# Esquematico.net
KiCad netlist of a schematic drawn in EasyEDA
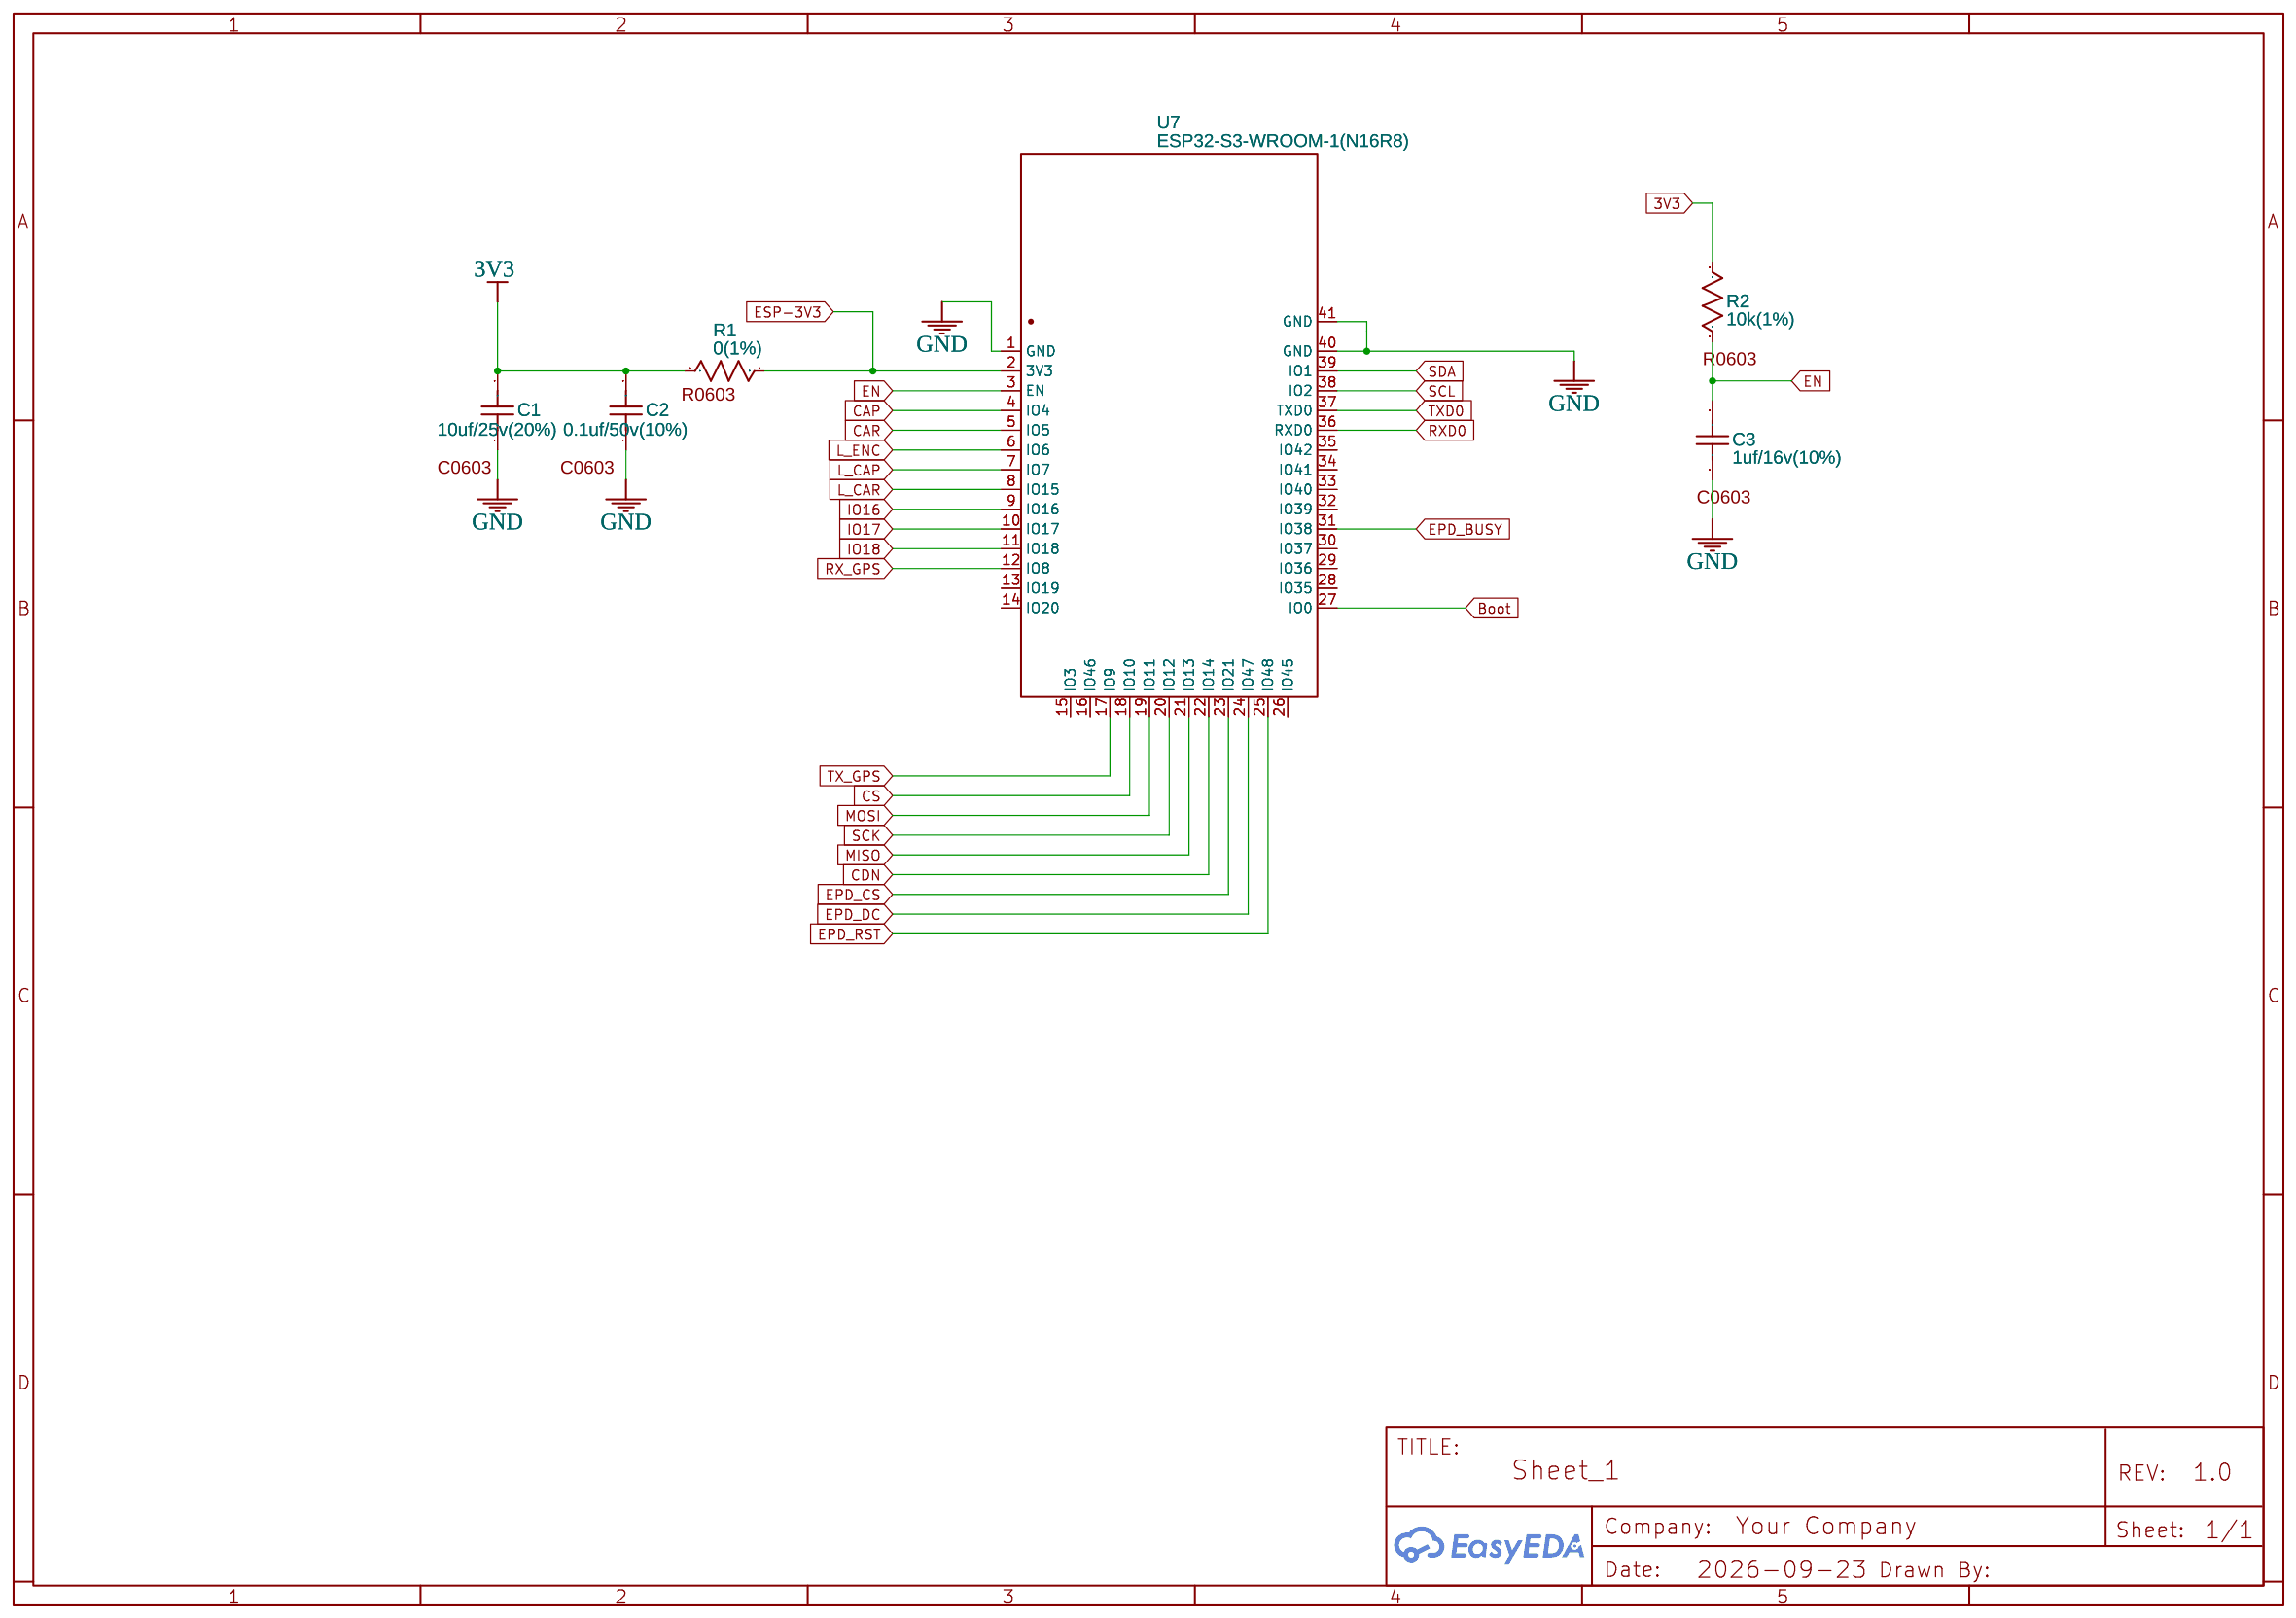
[diagram p0: ESP32-S3]
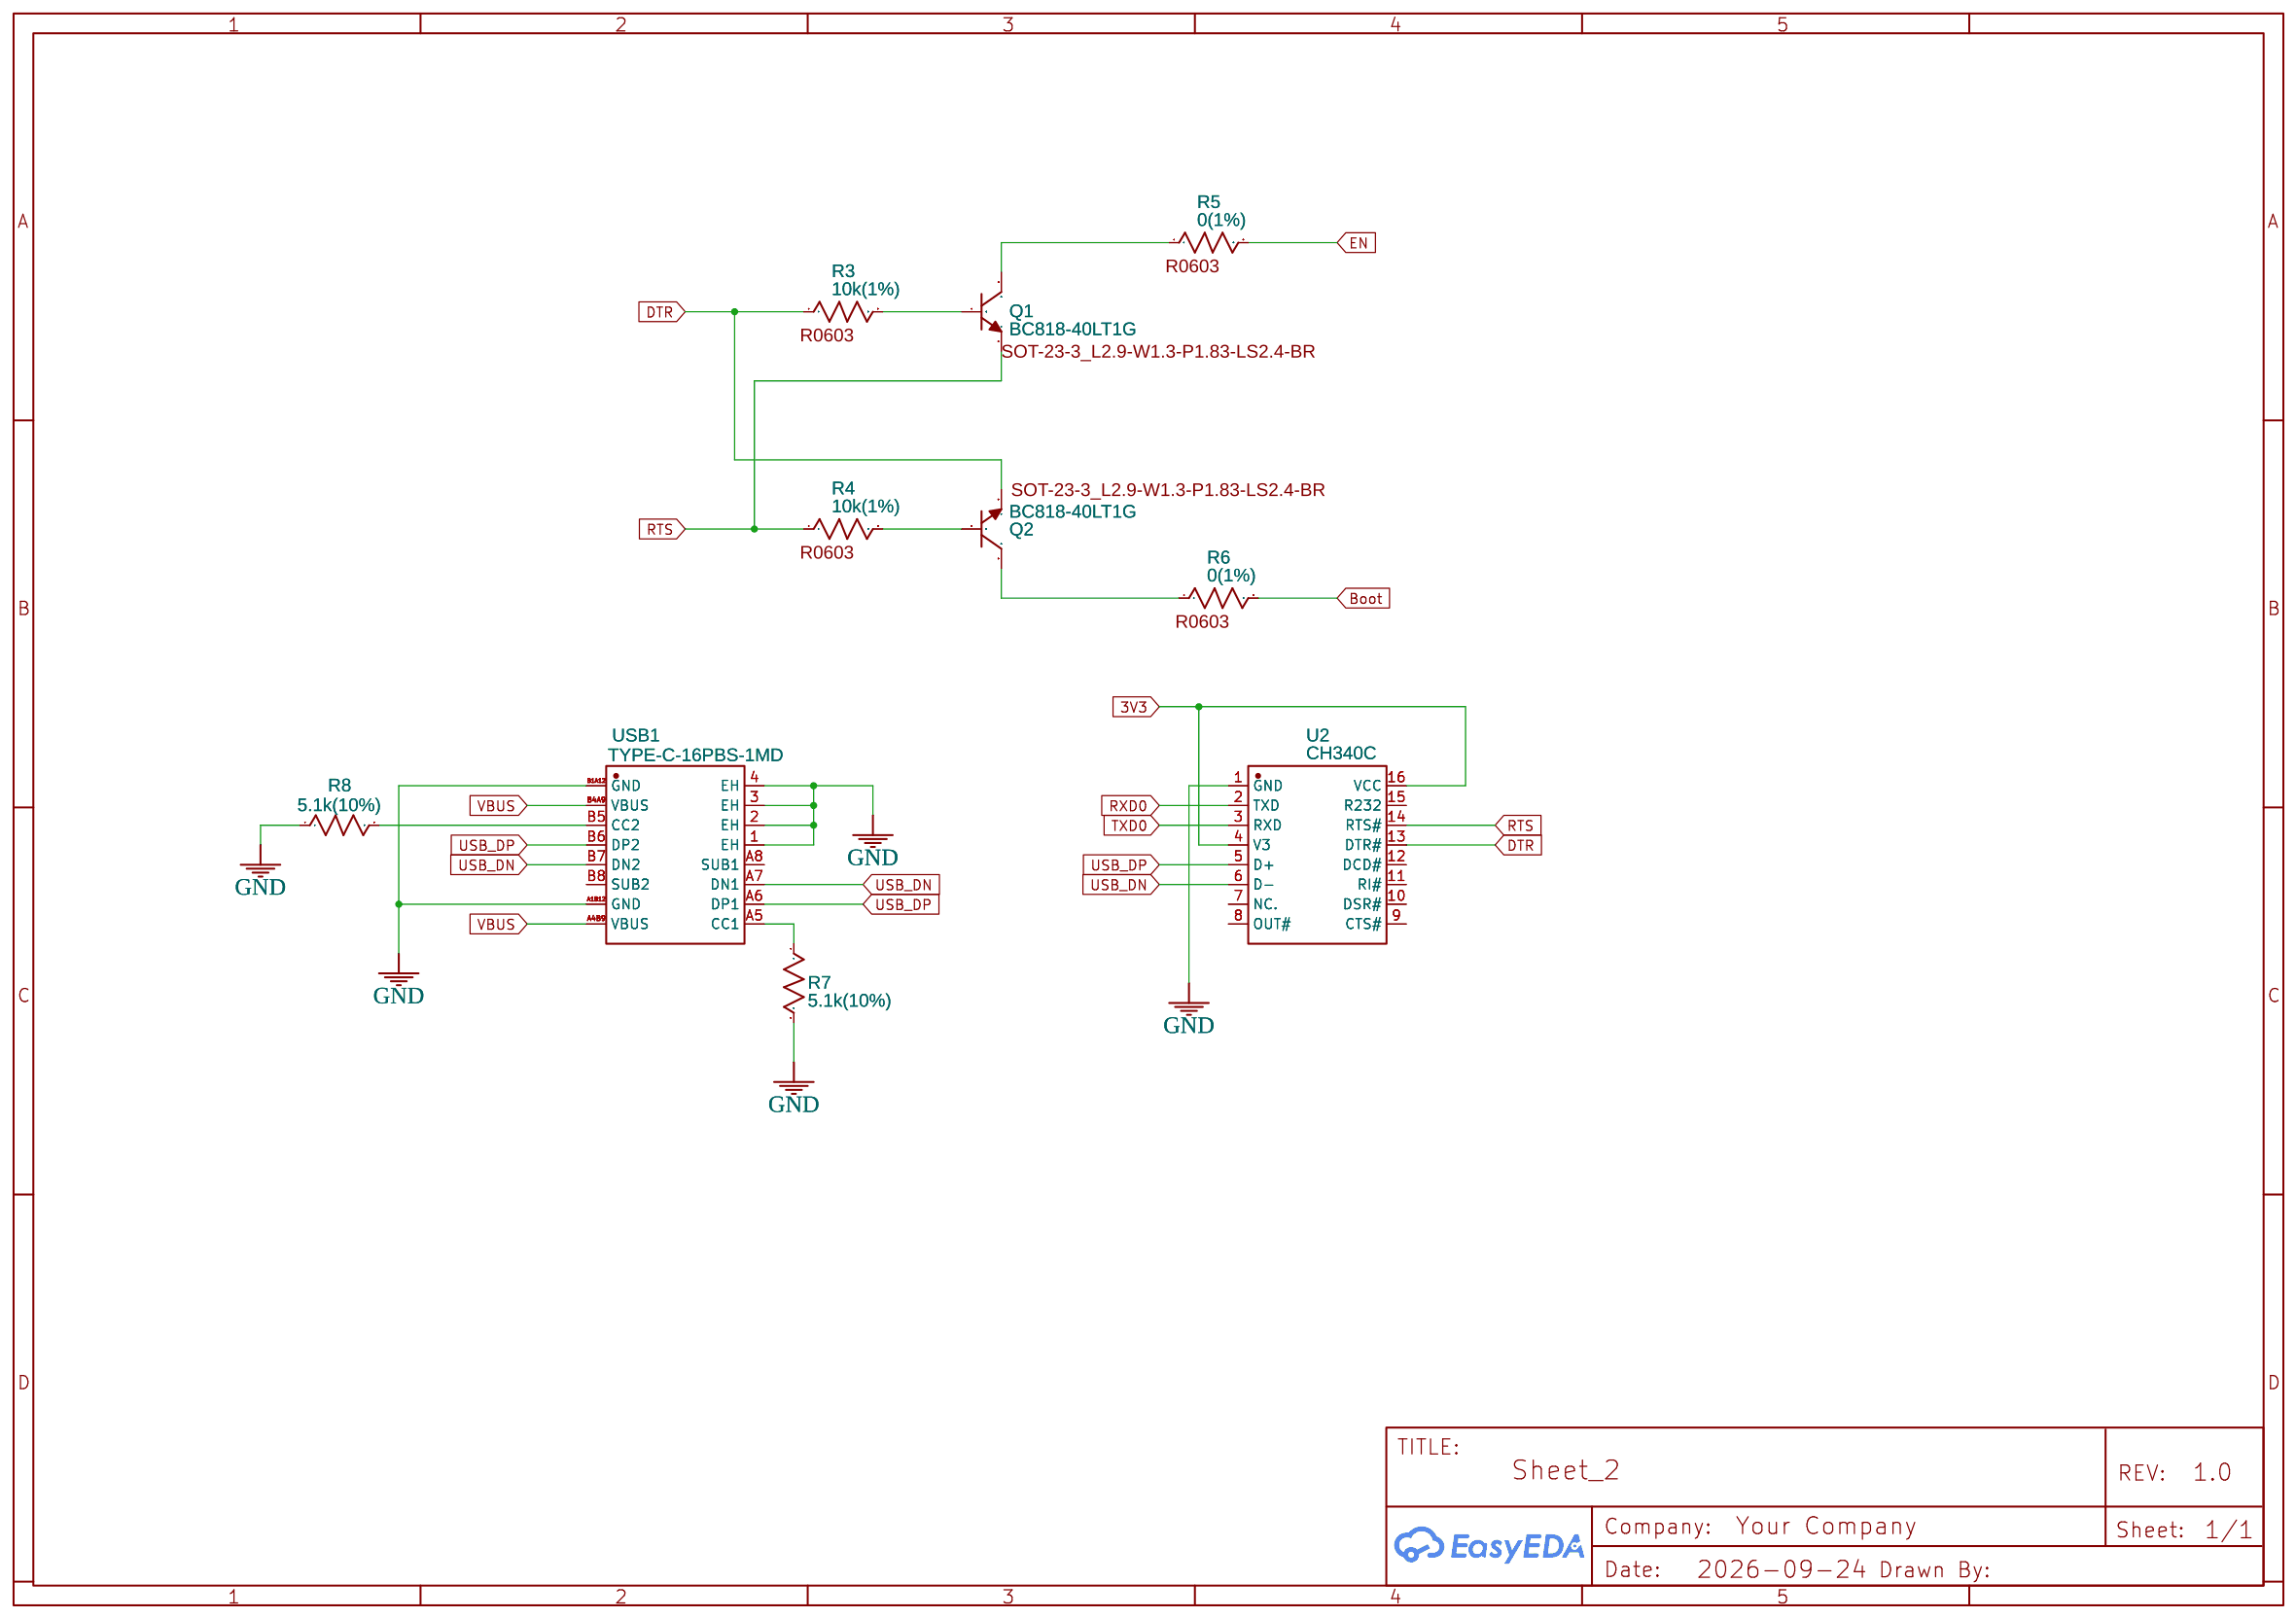
[diagram p1: Programacion]
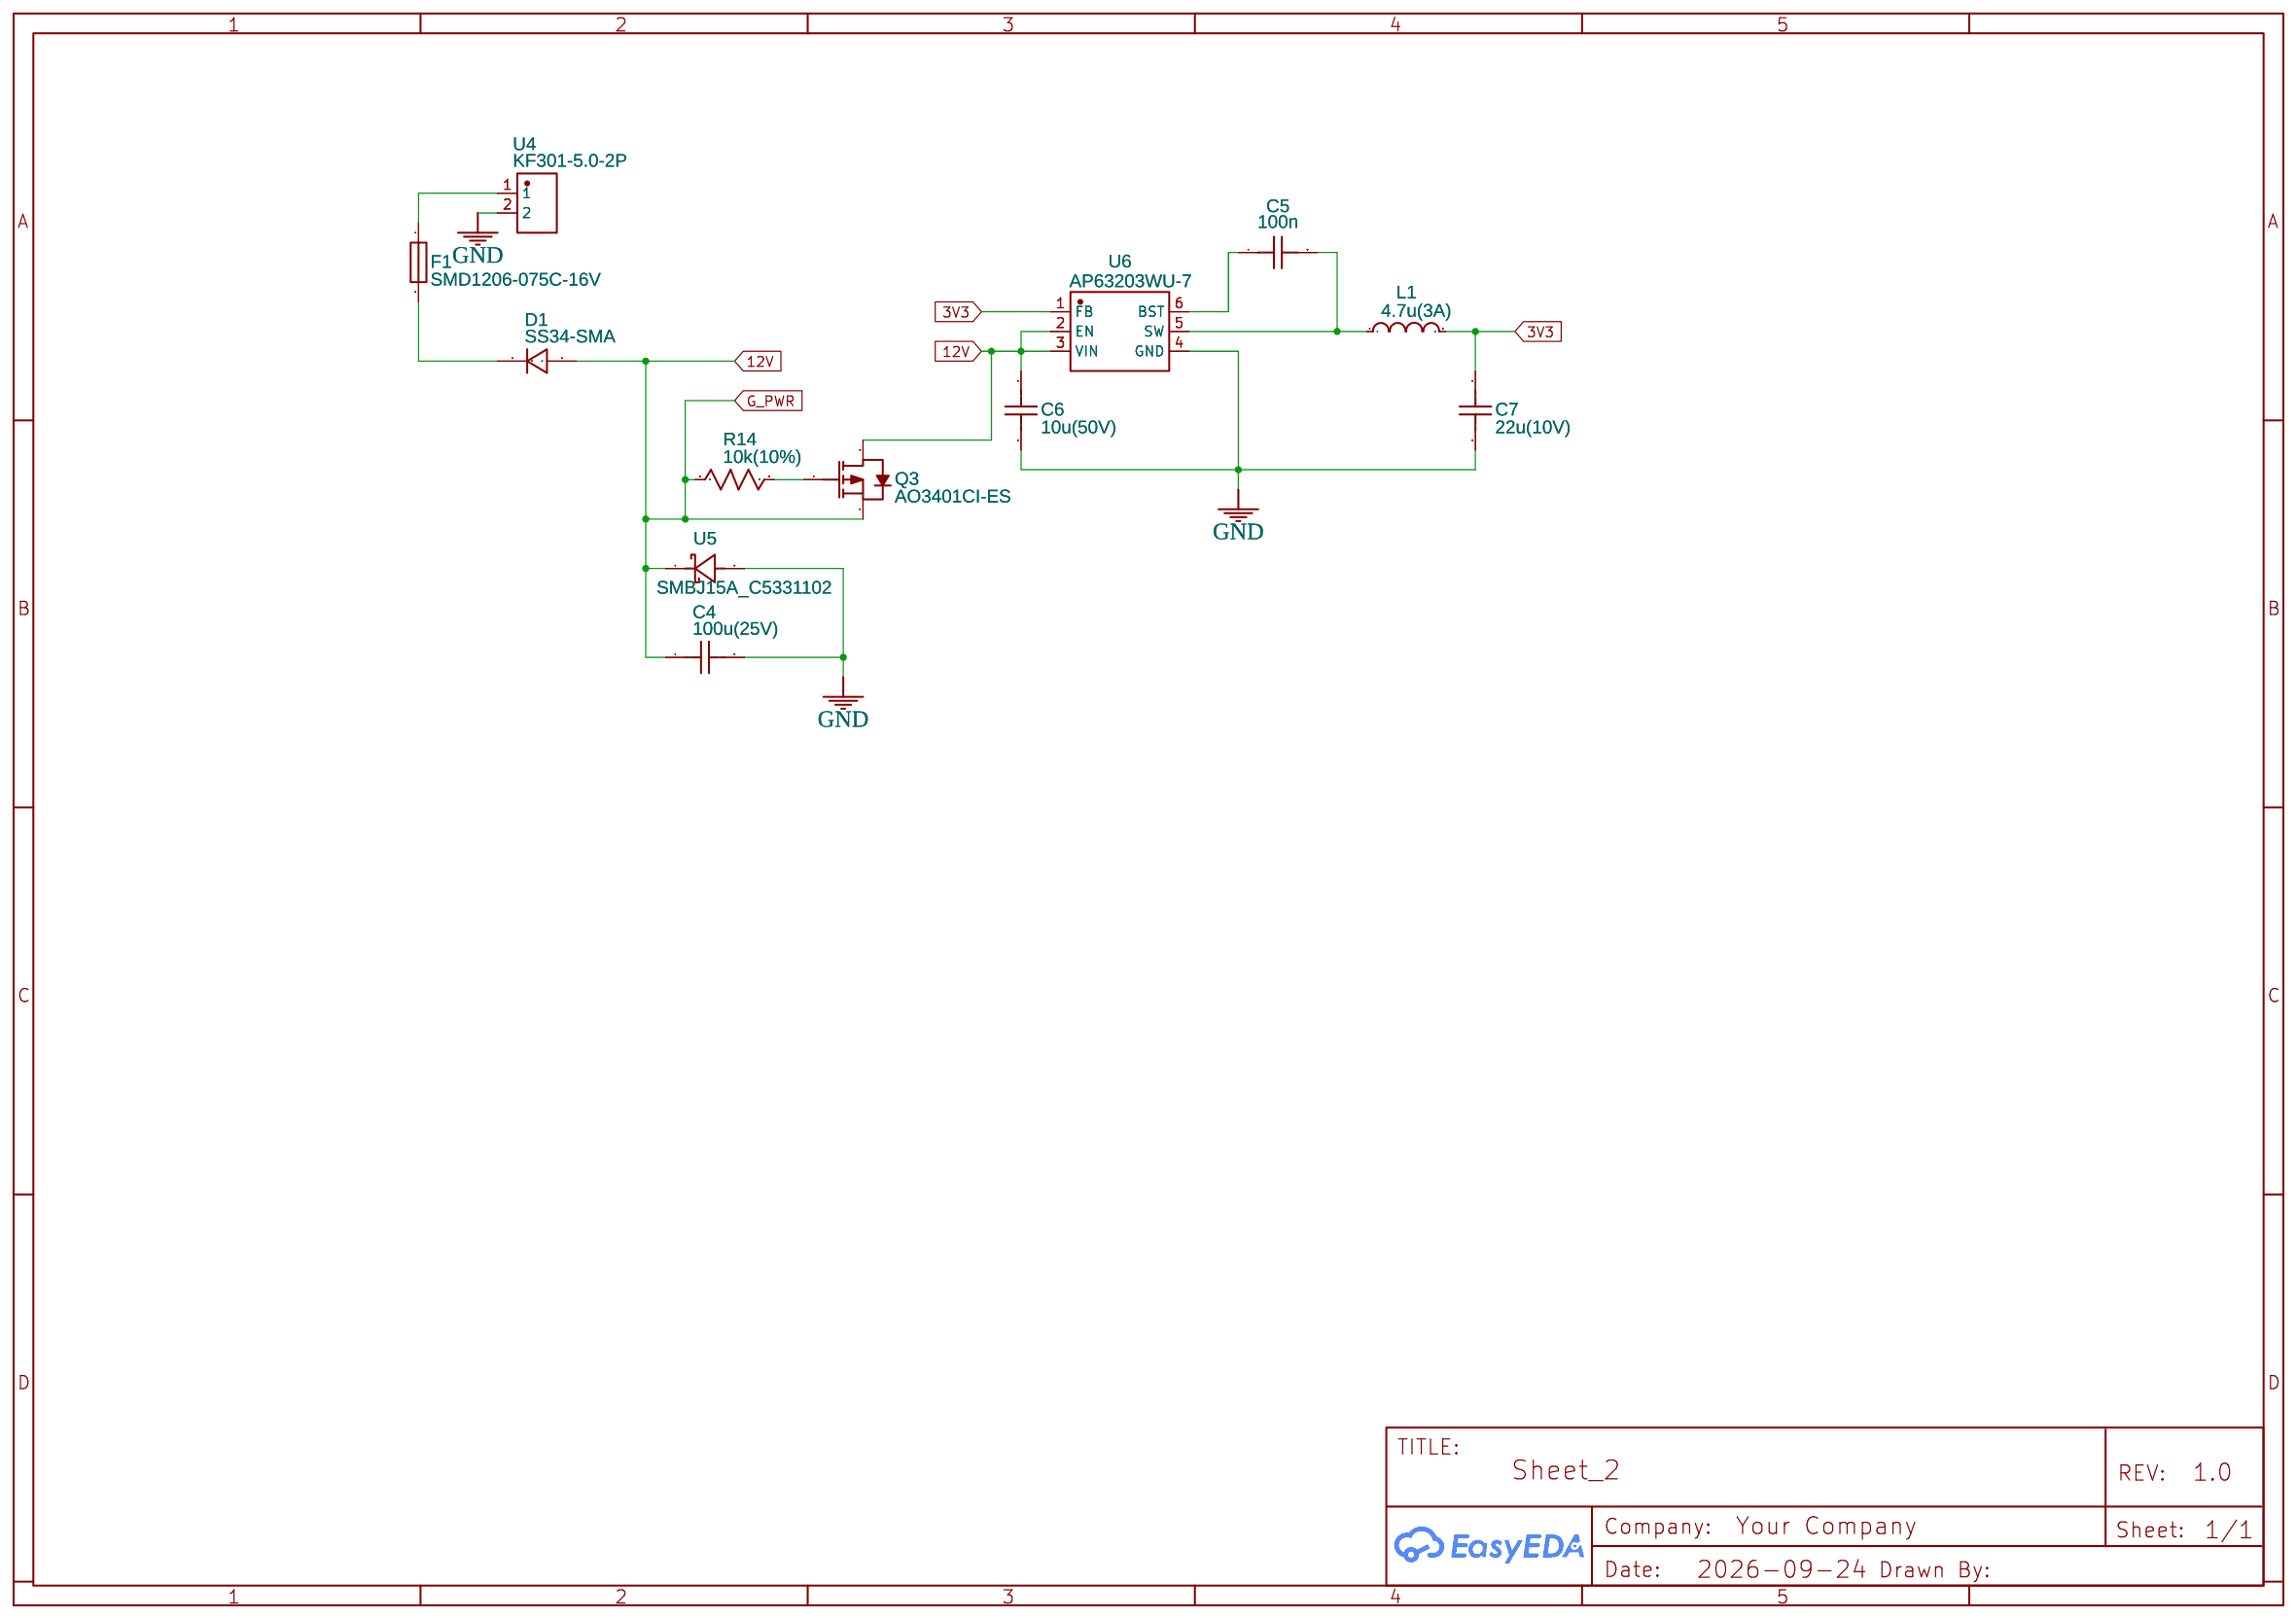
[diagram p2: 12V a 3V3]
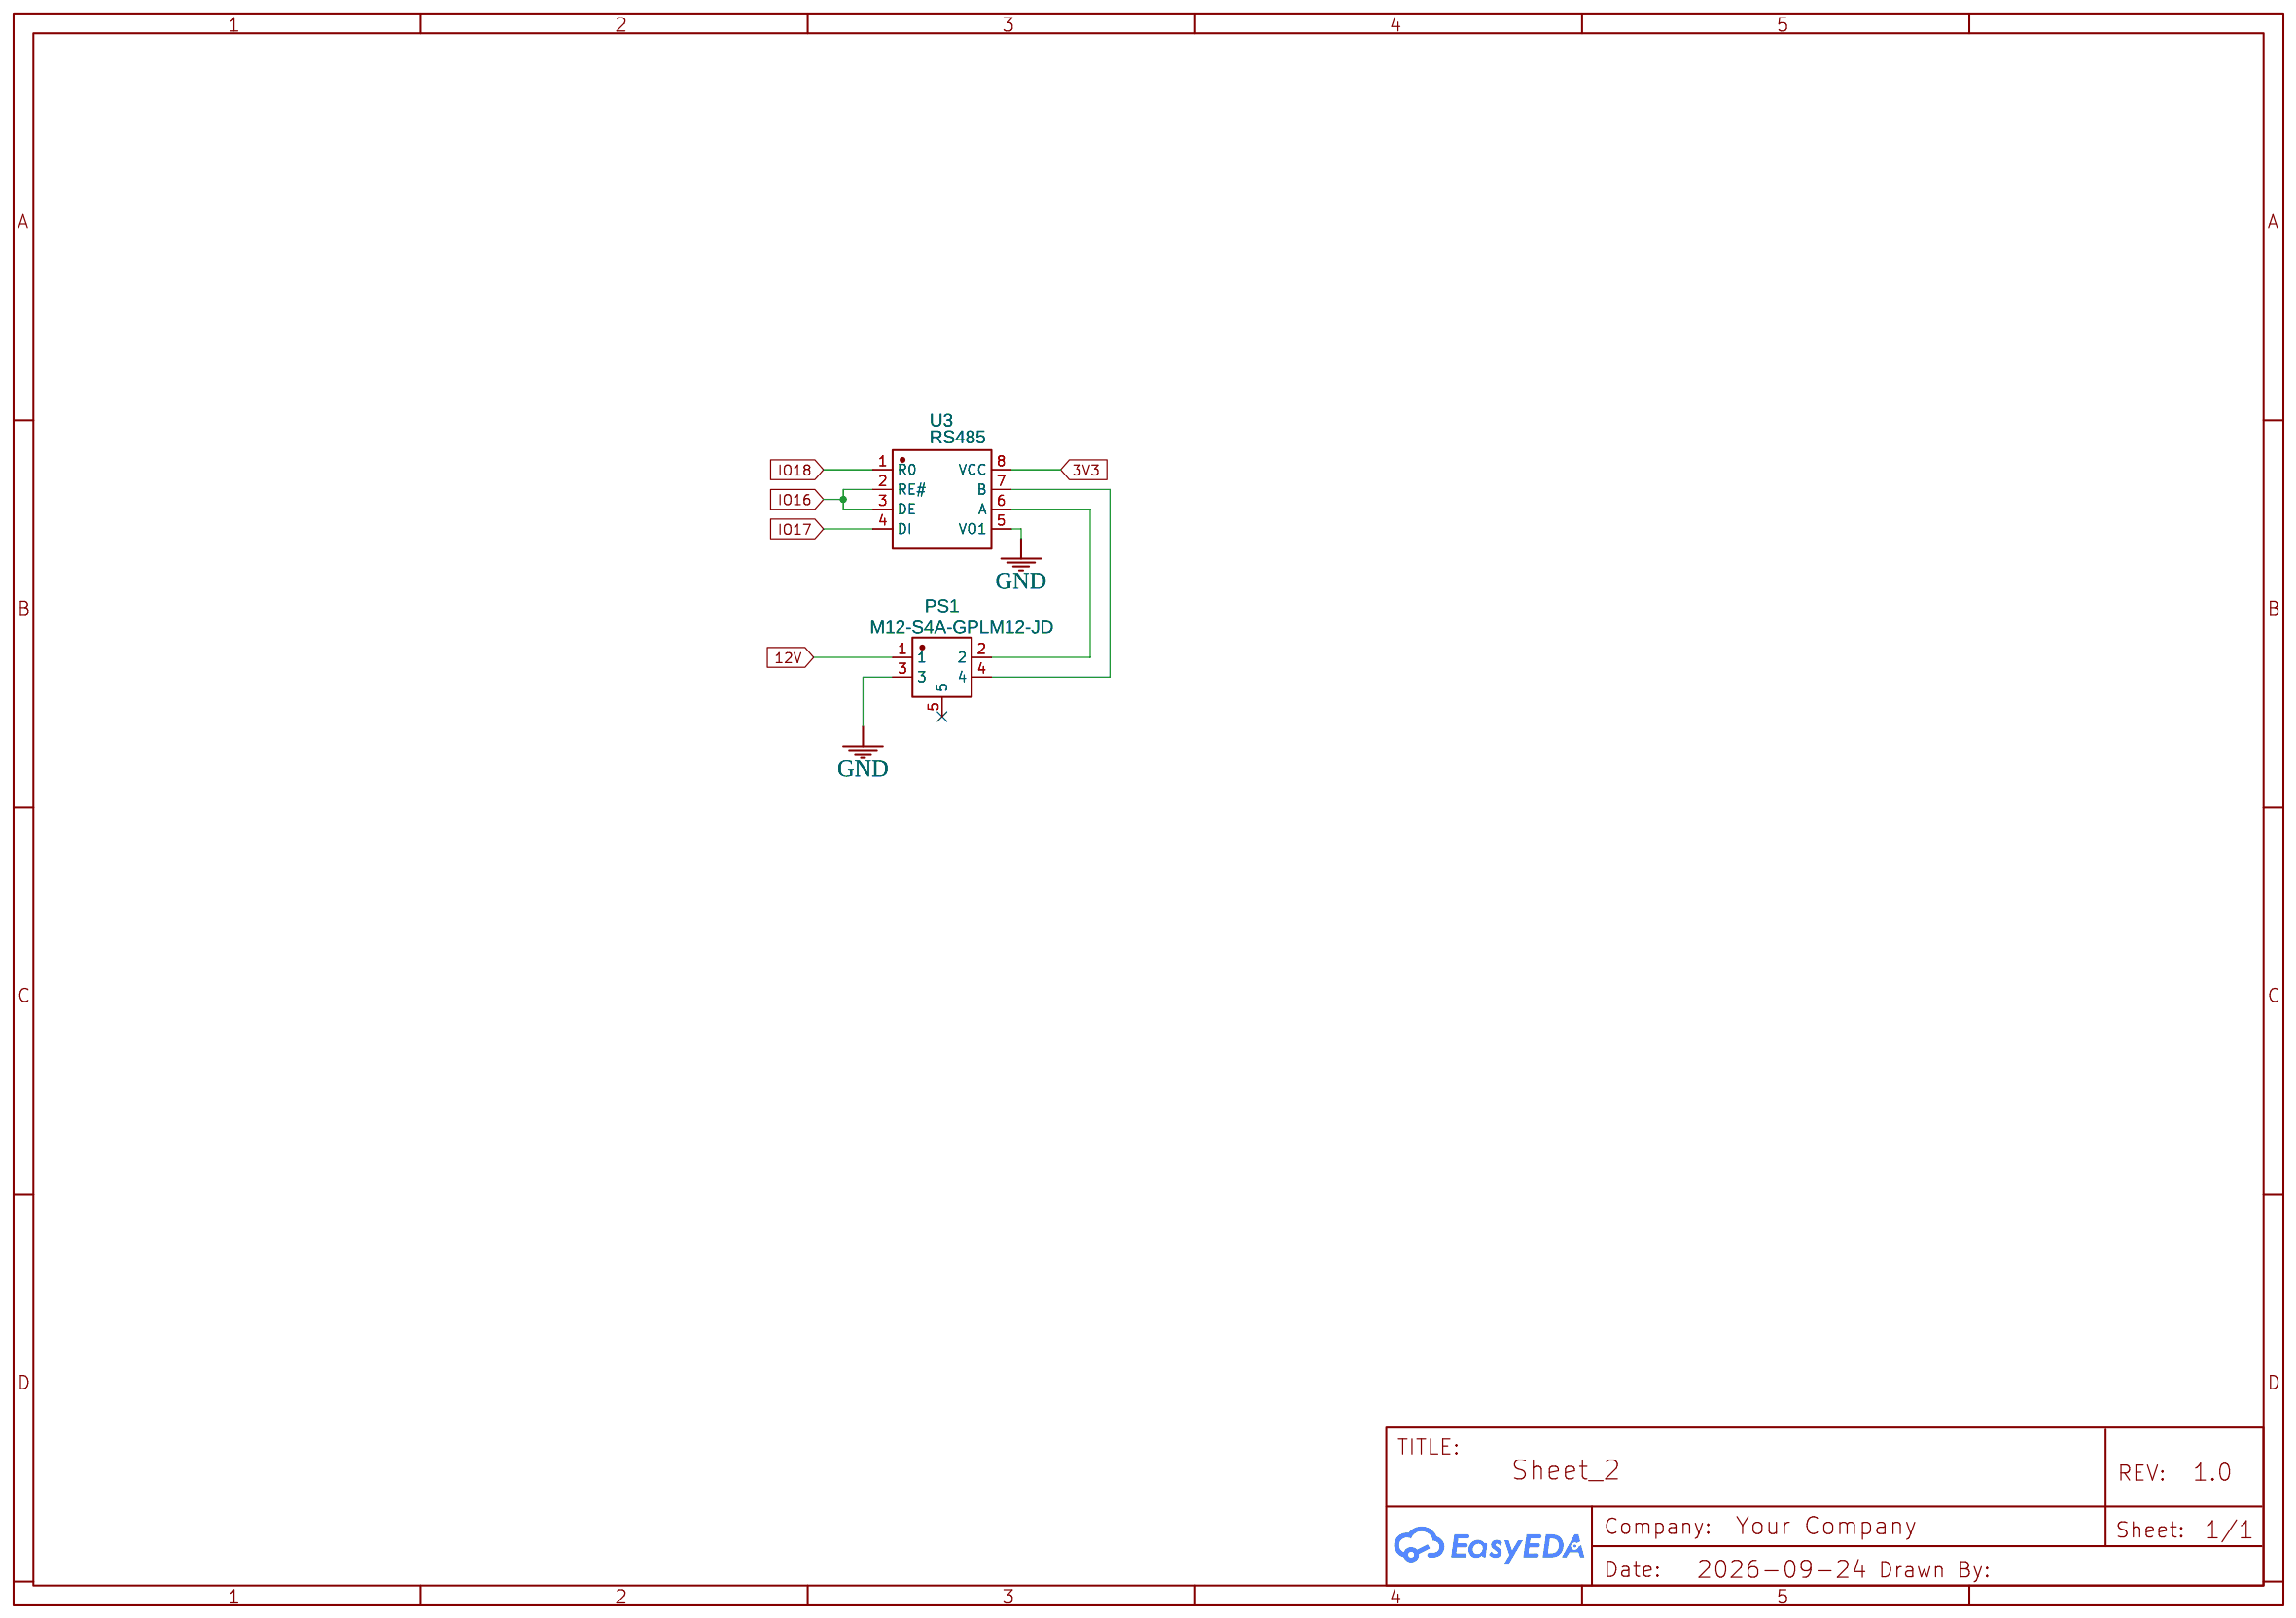
[diagram p3: sensor NPK, PH, HUMEDAD]
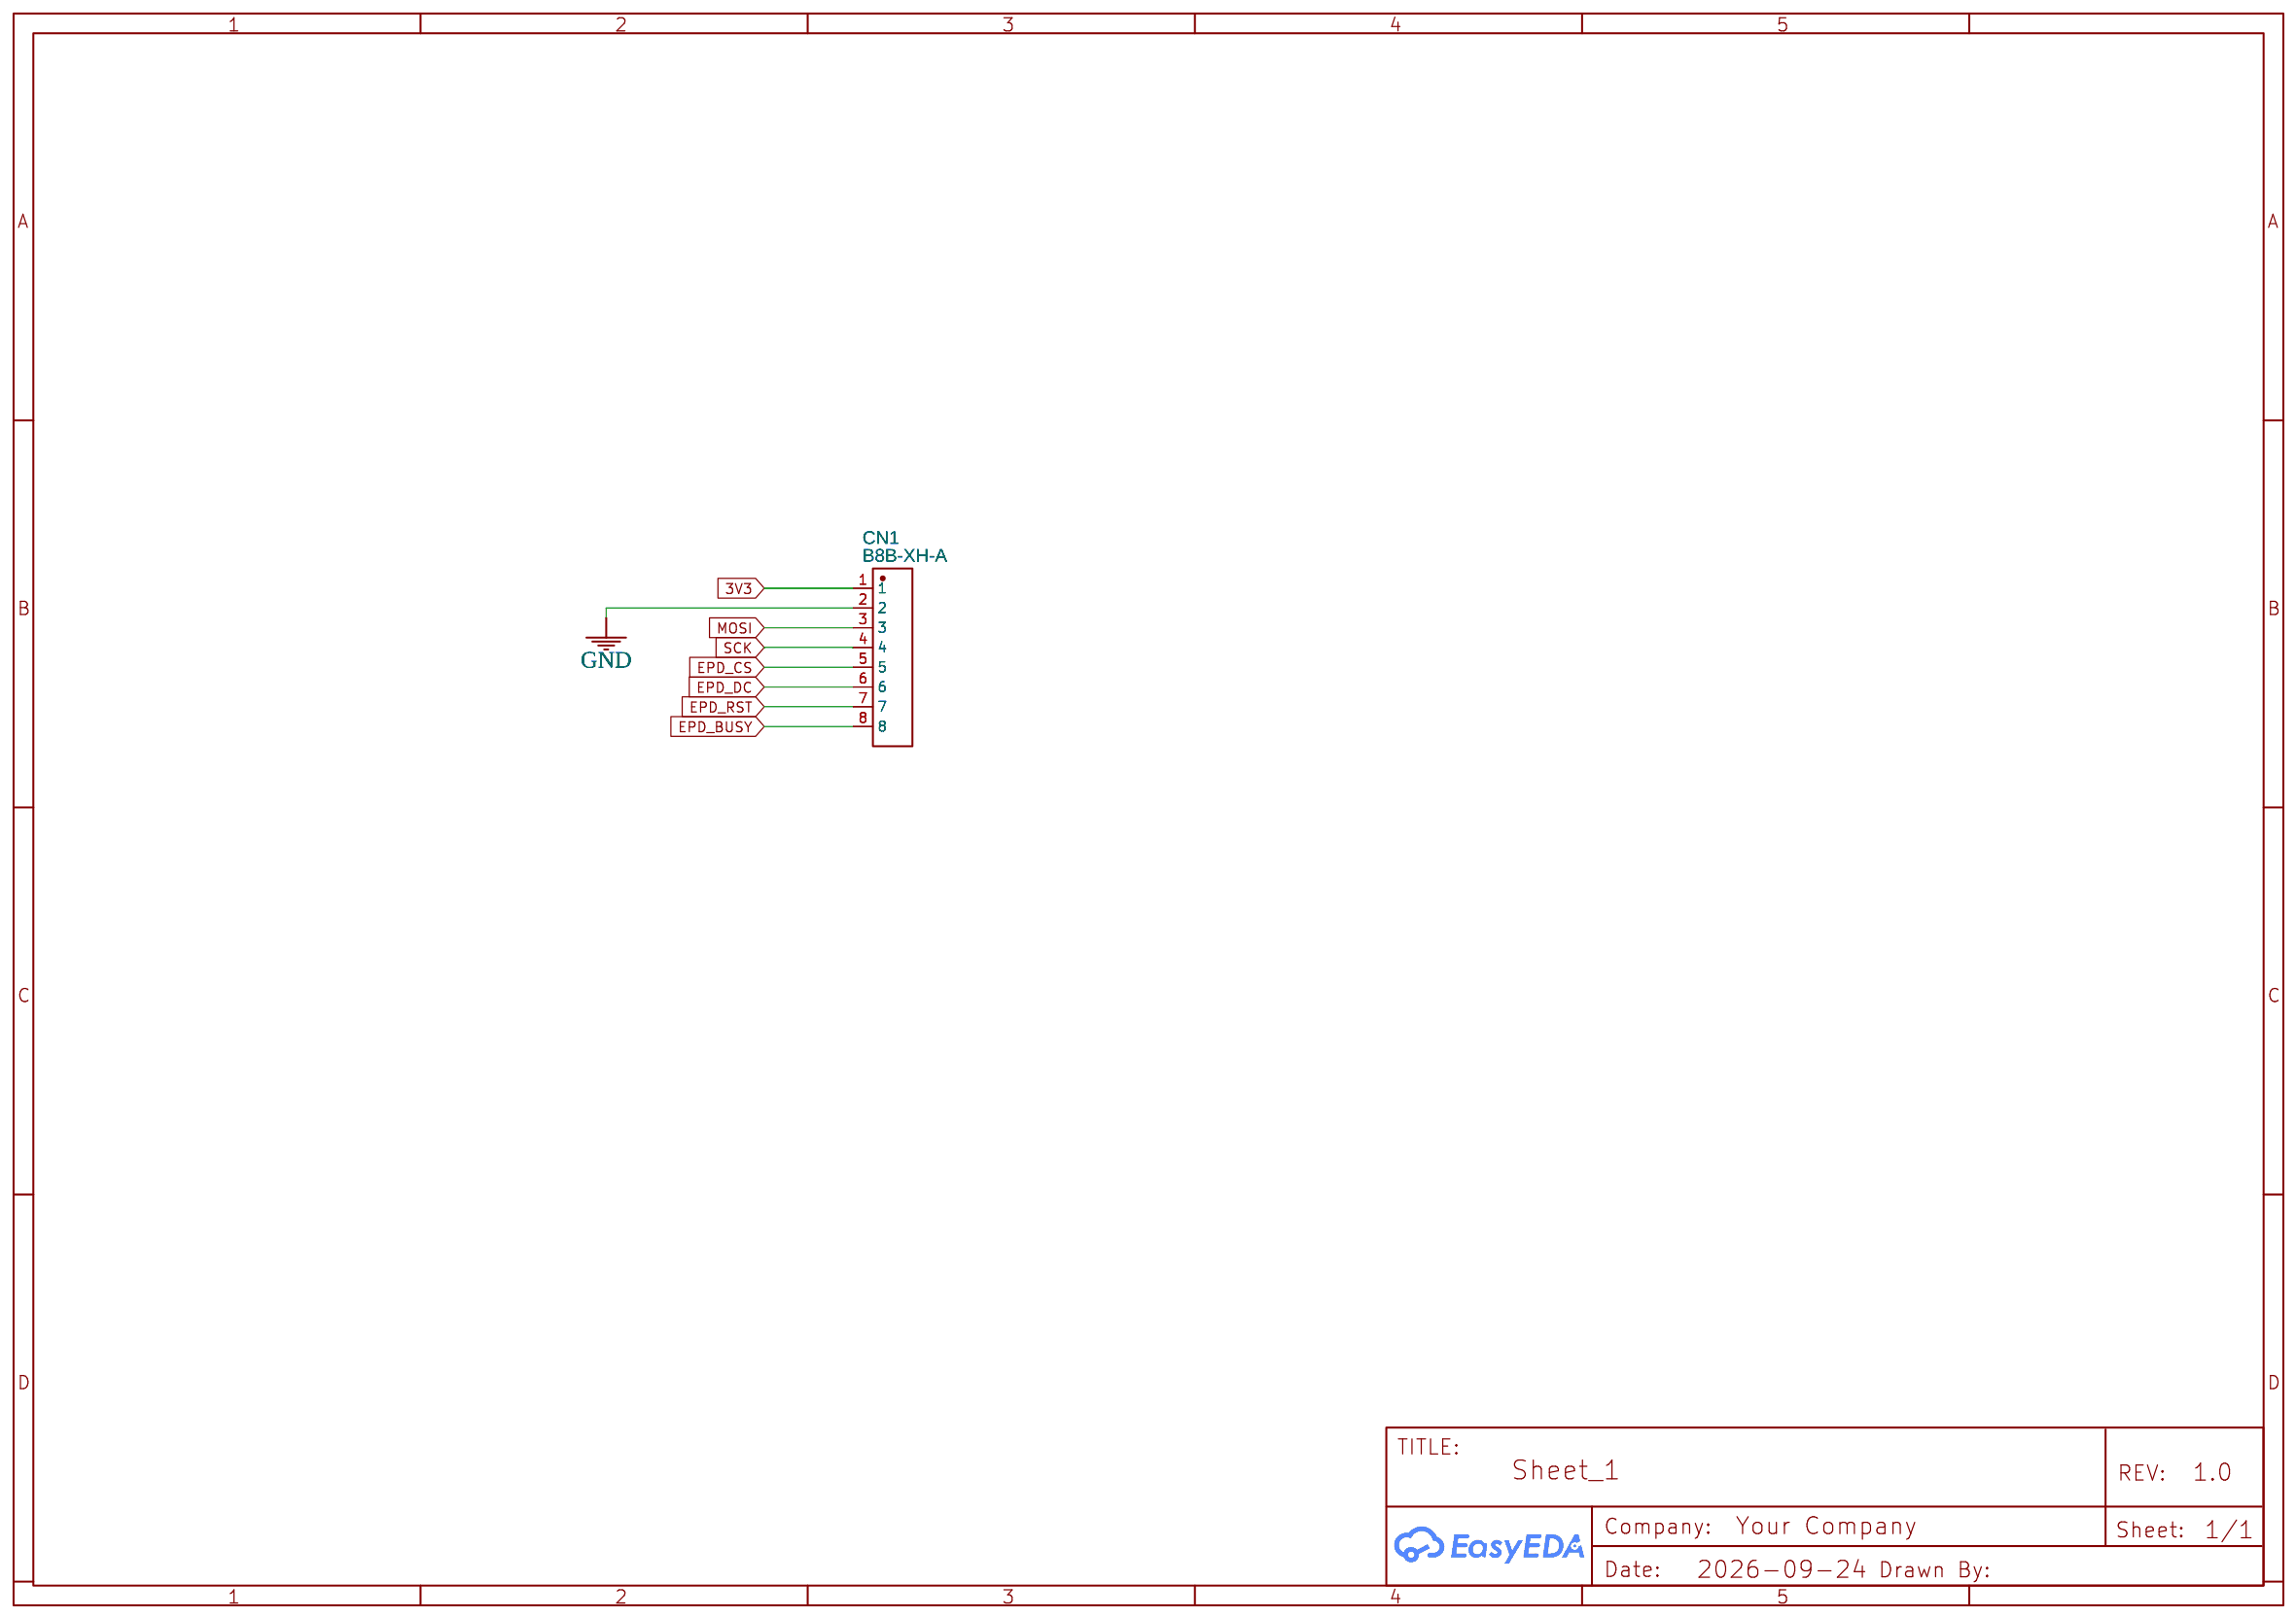
[diagram p4: EPAPER]
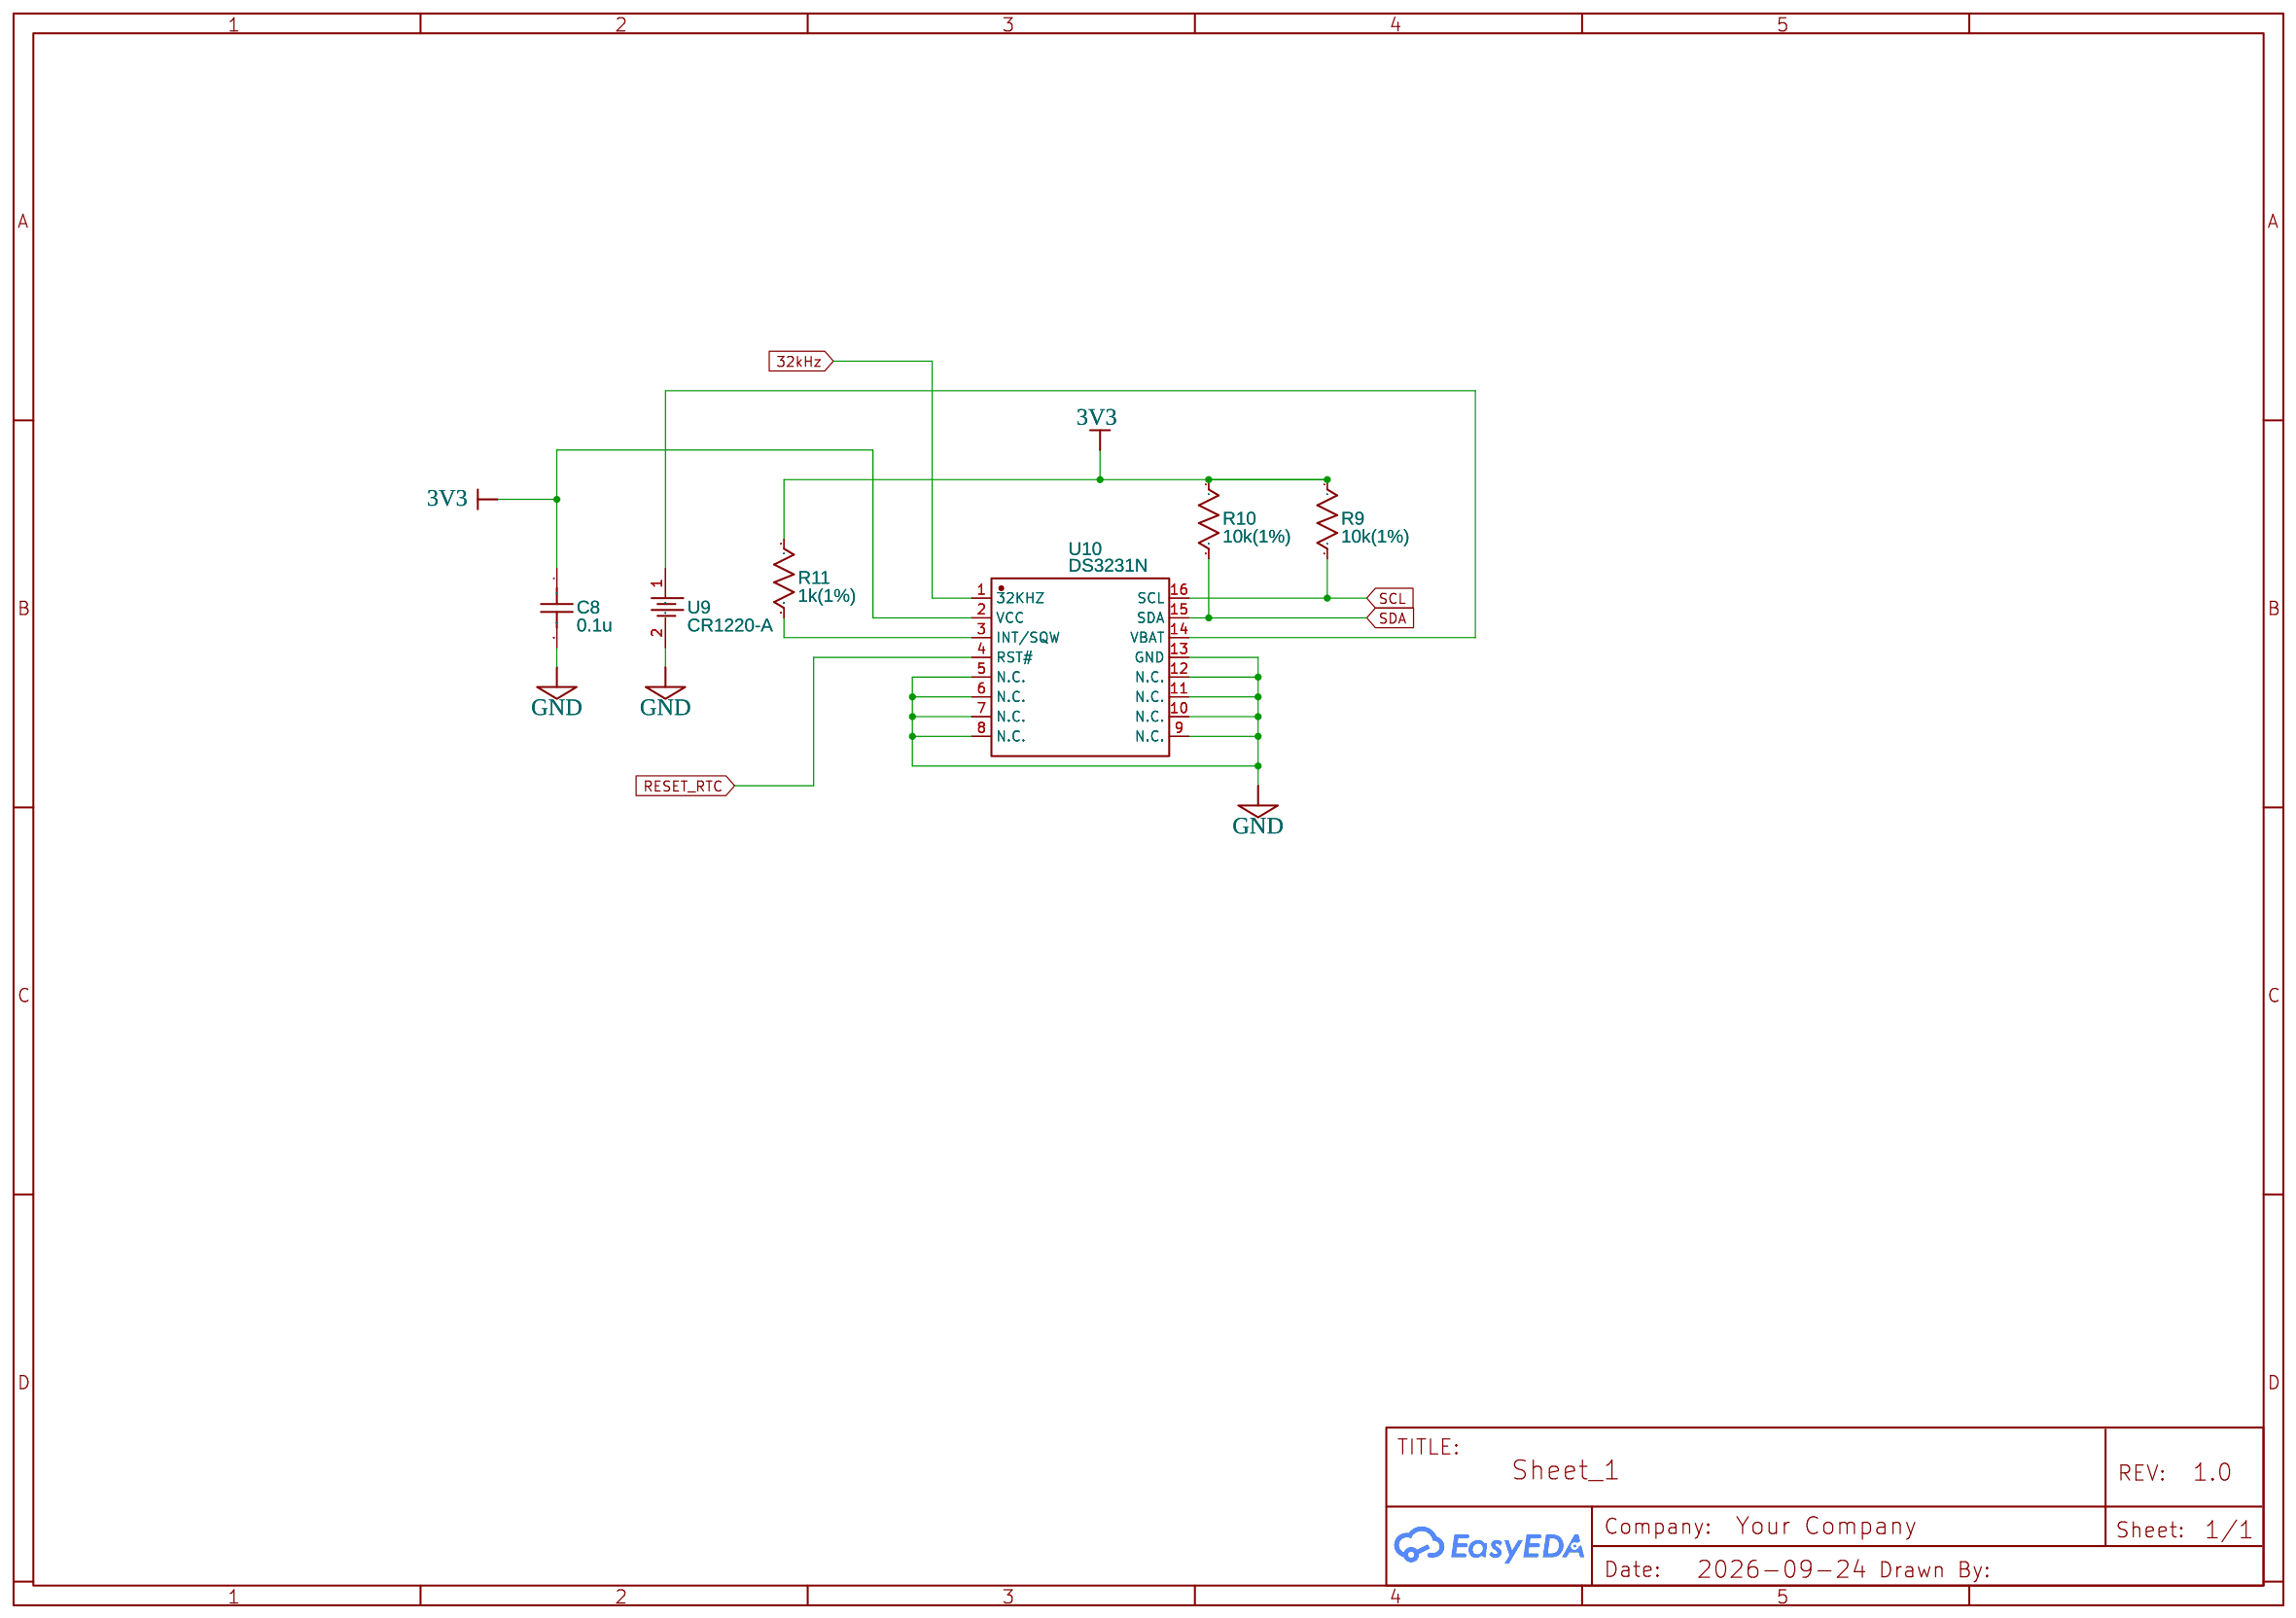
[diagram p5: Reloj]
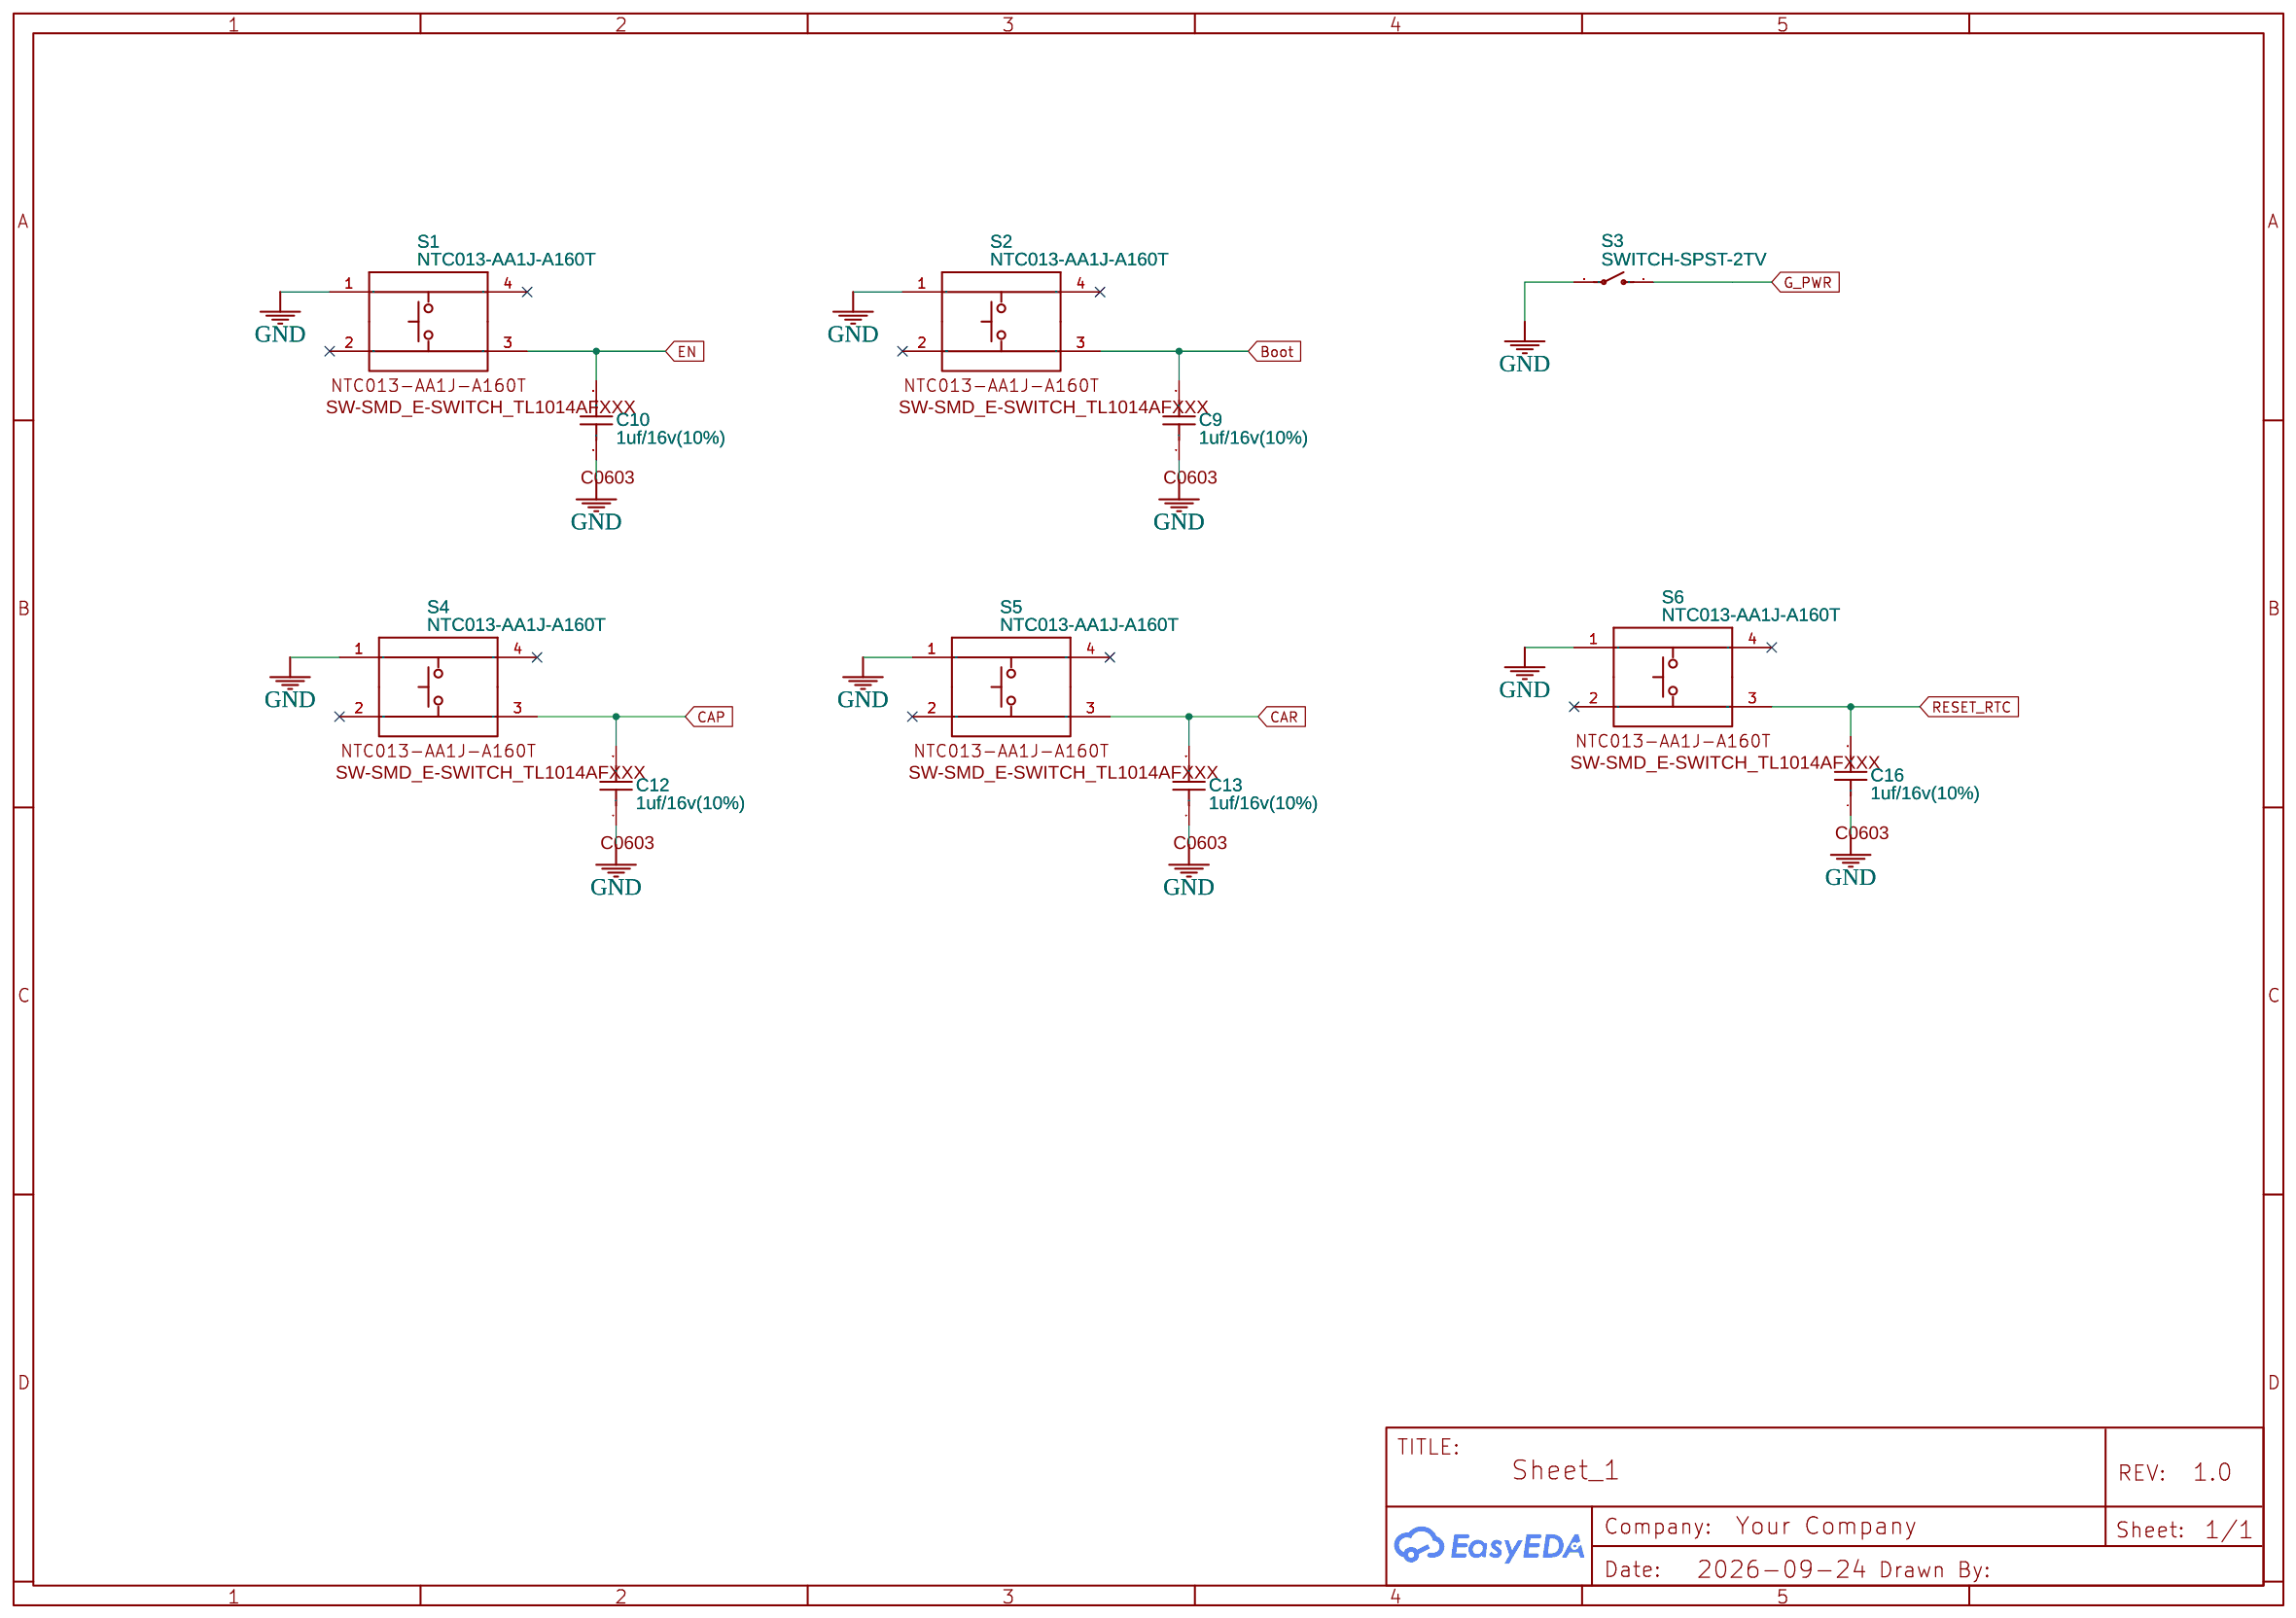
[diagram p6: Botones]
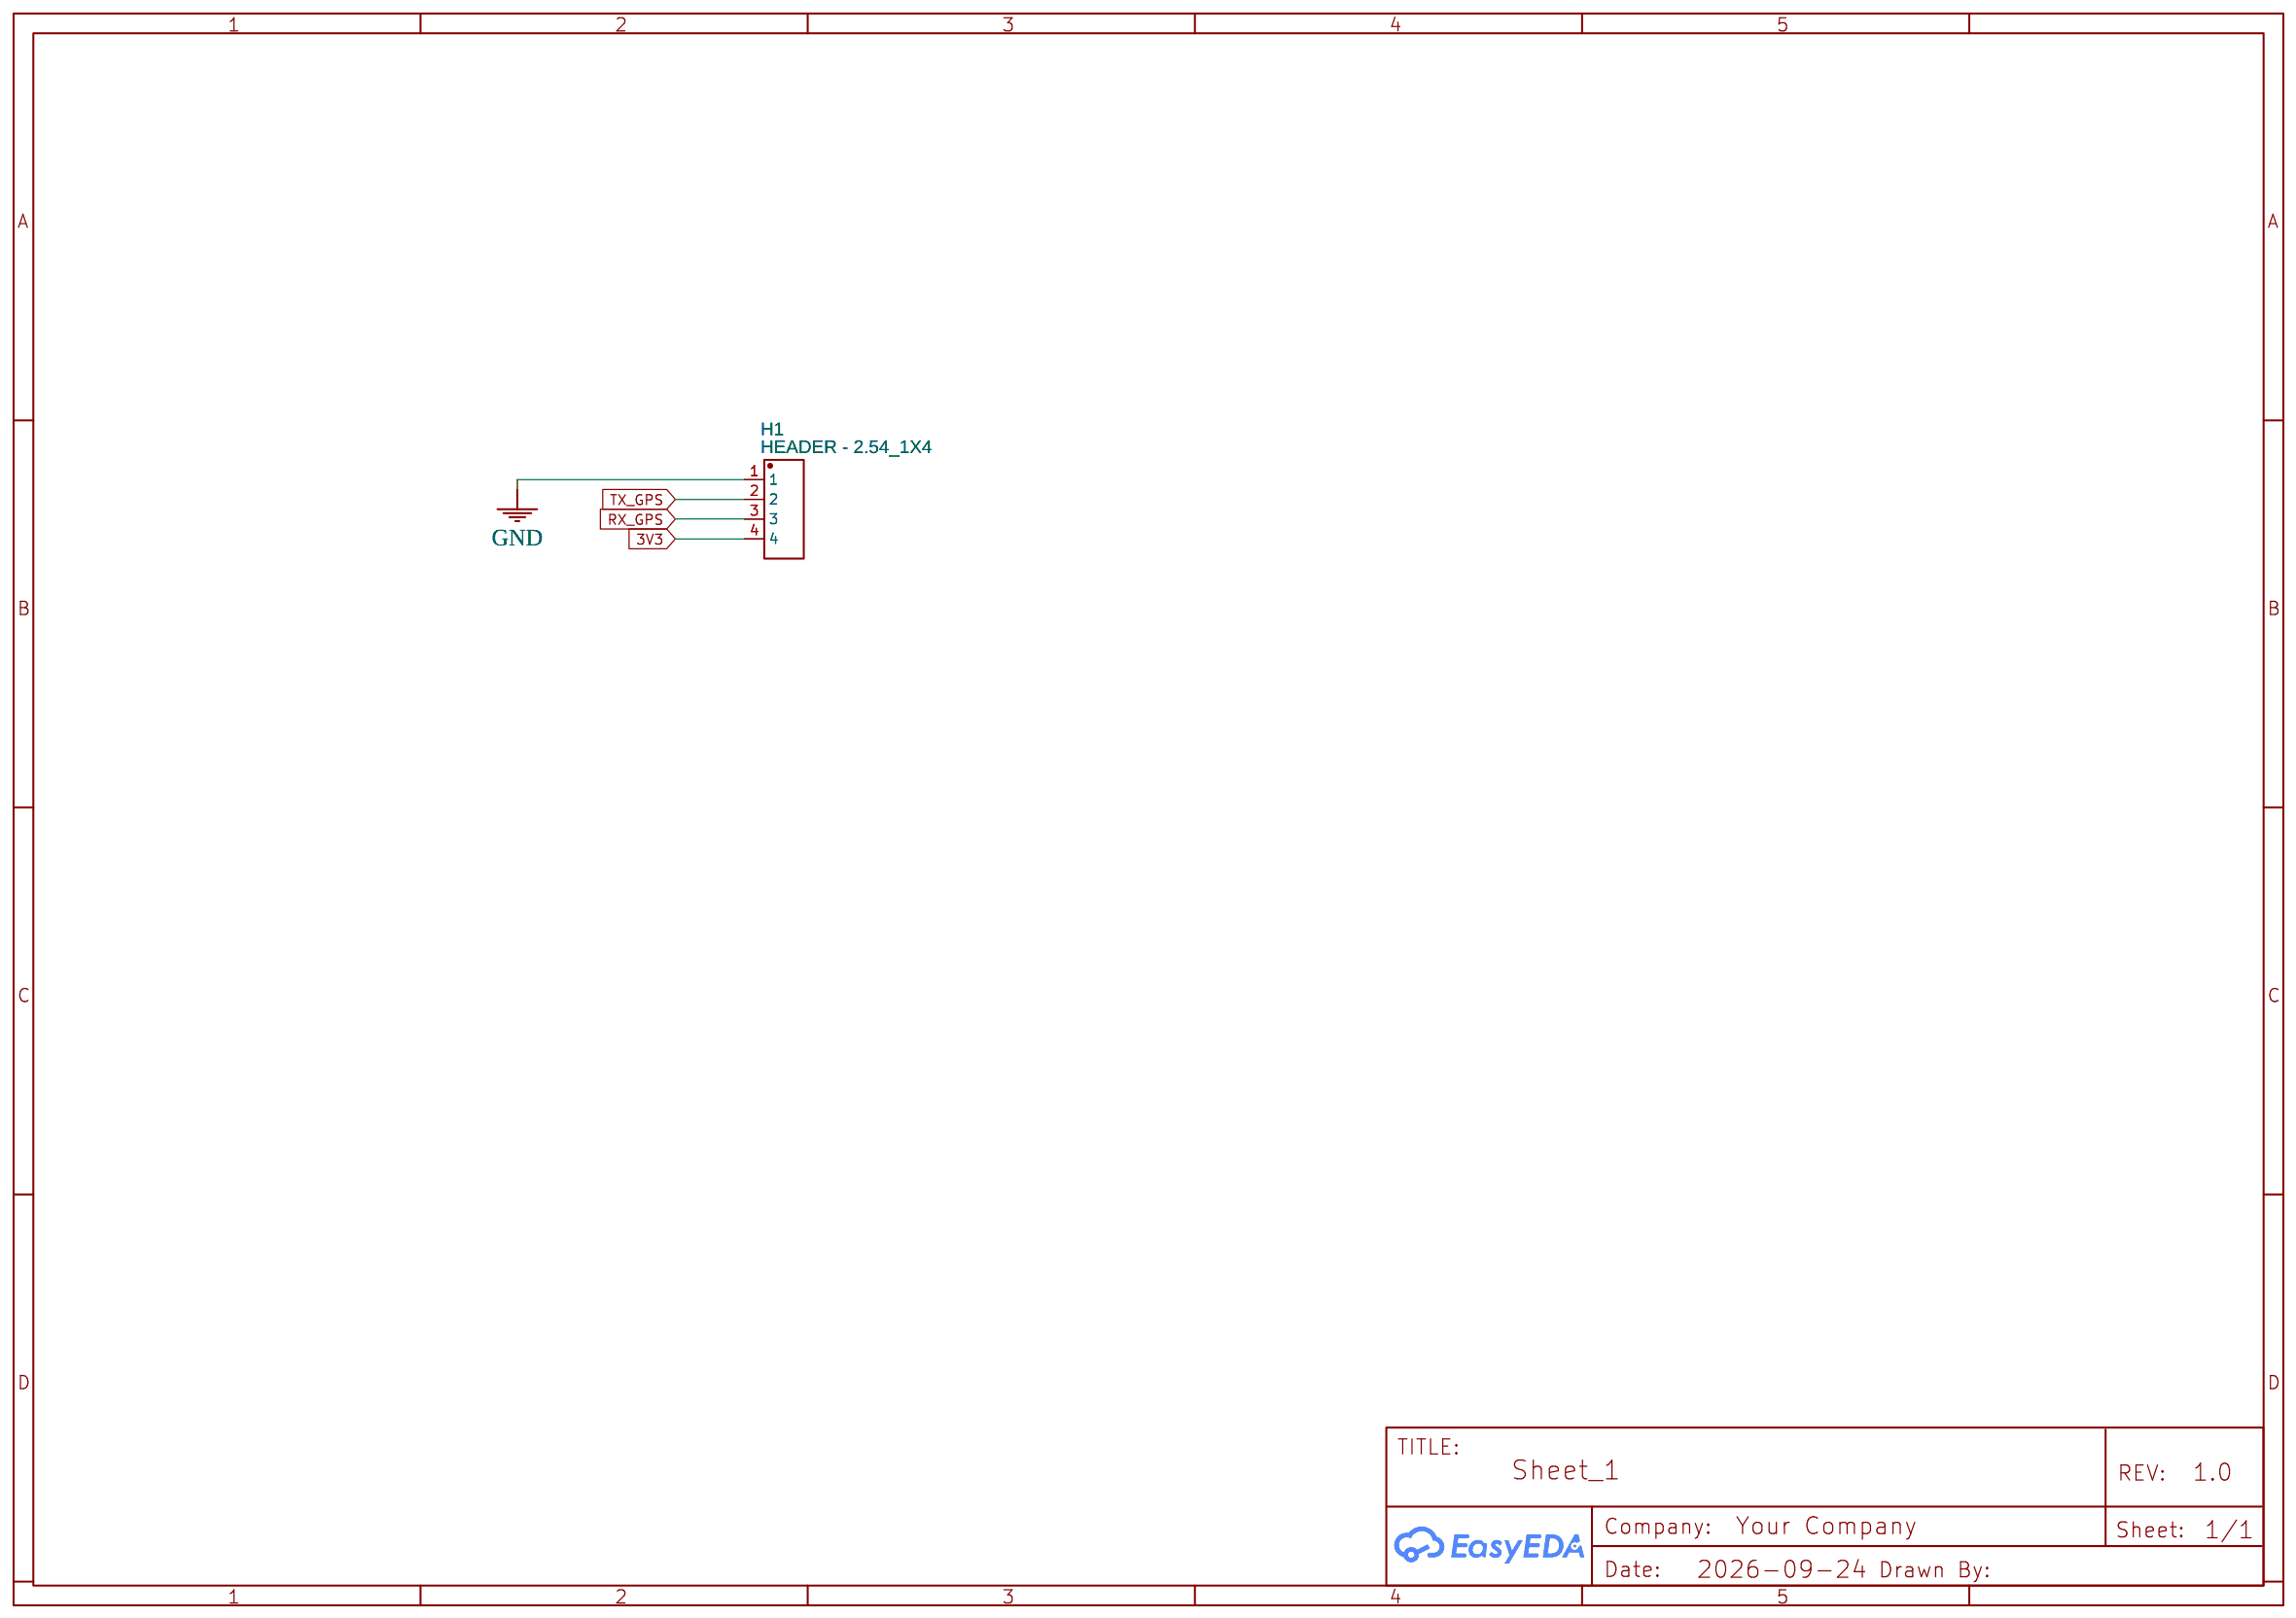
[diagram p7: GPS]
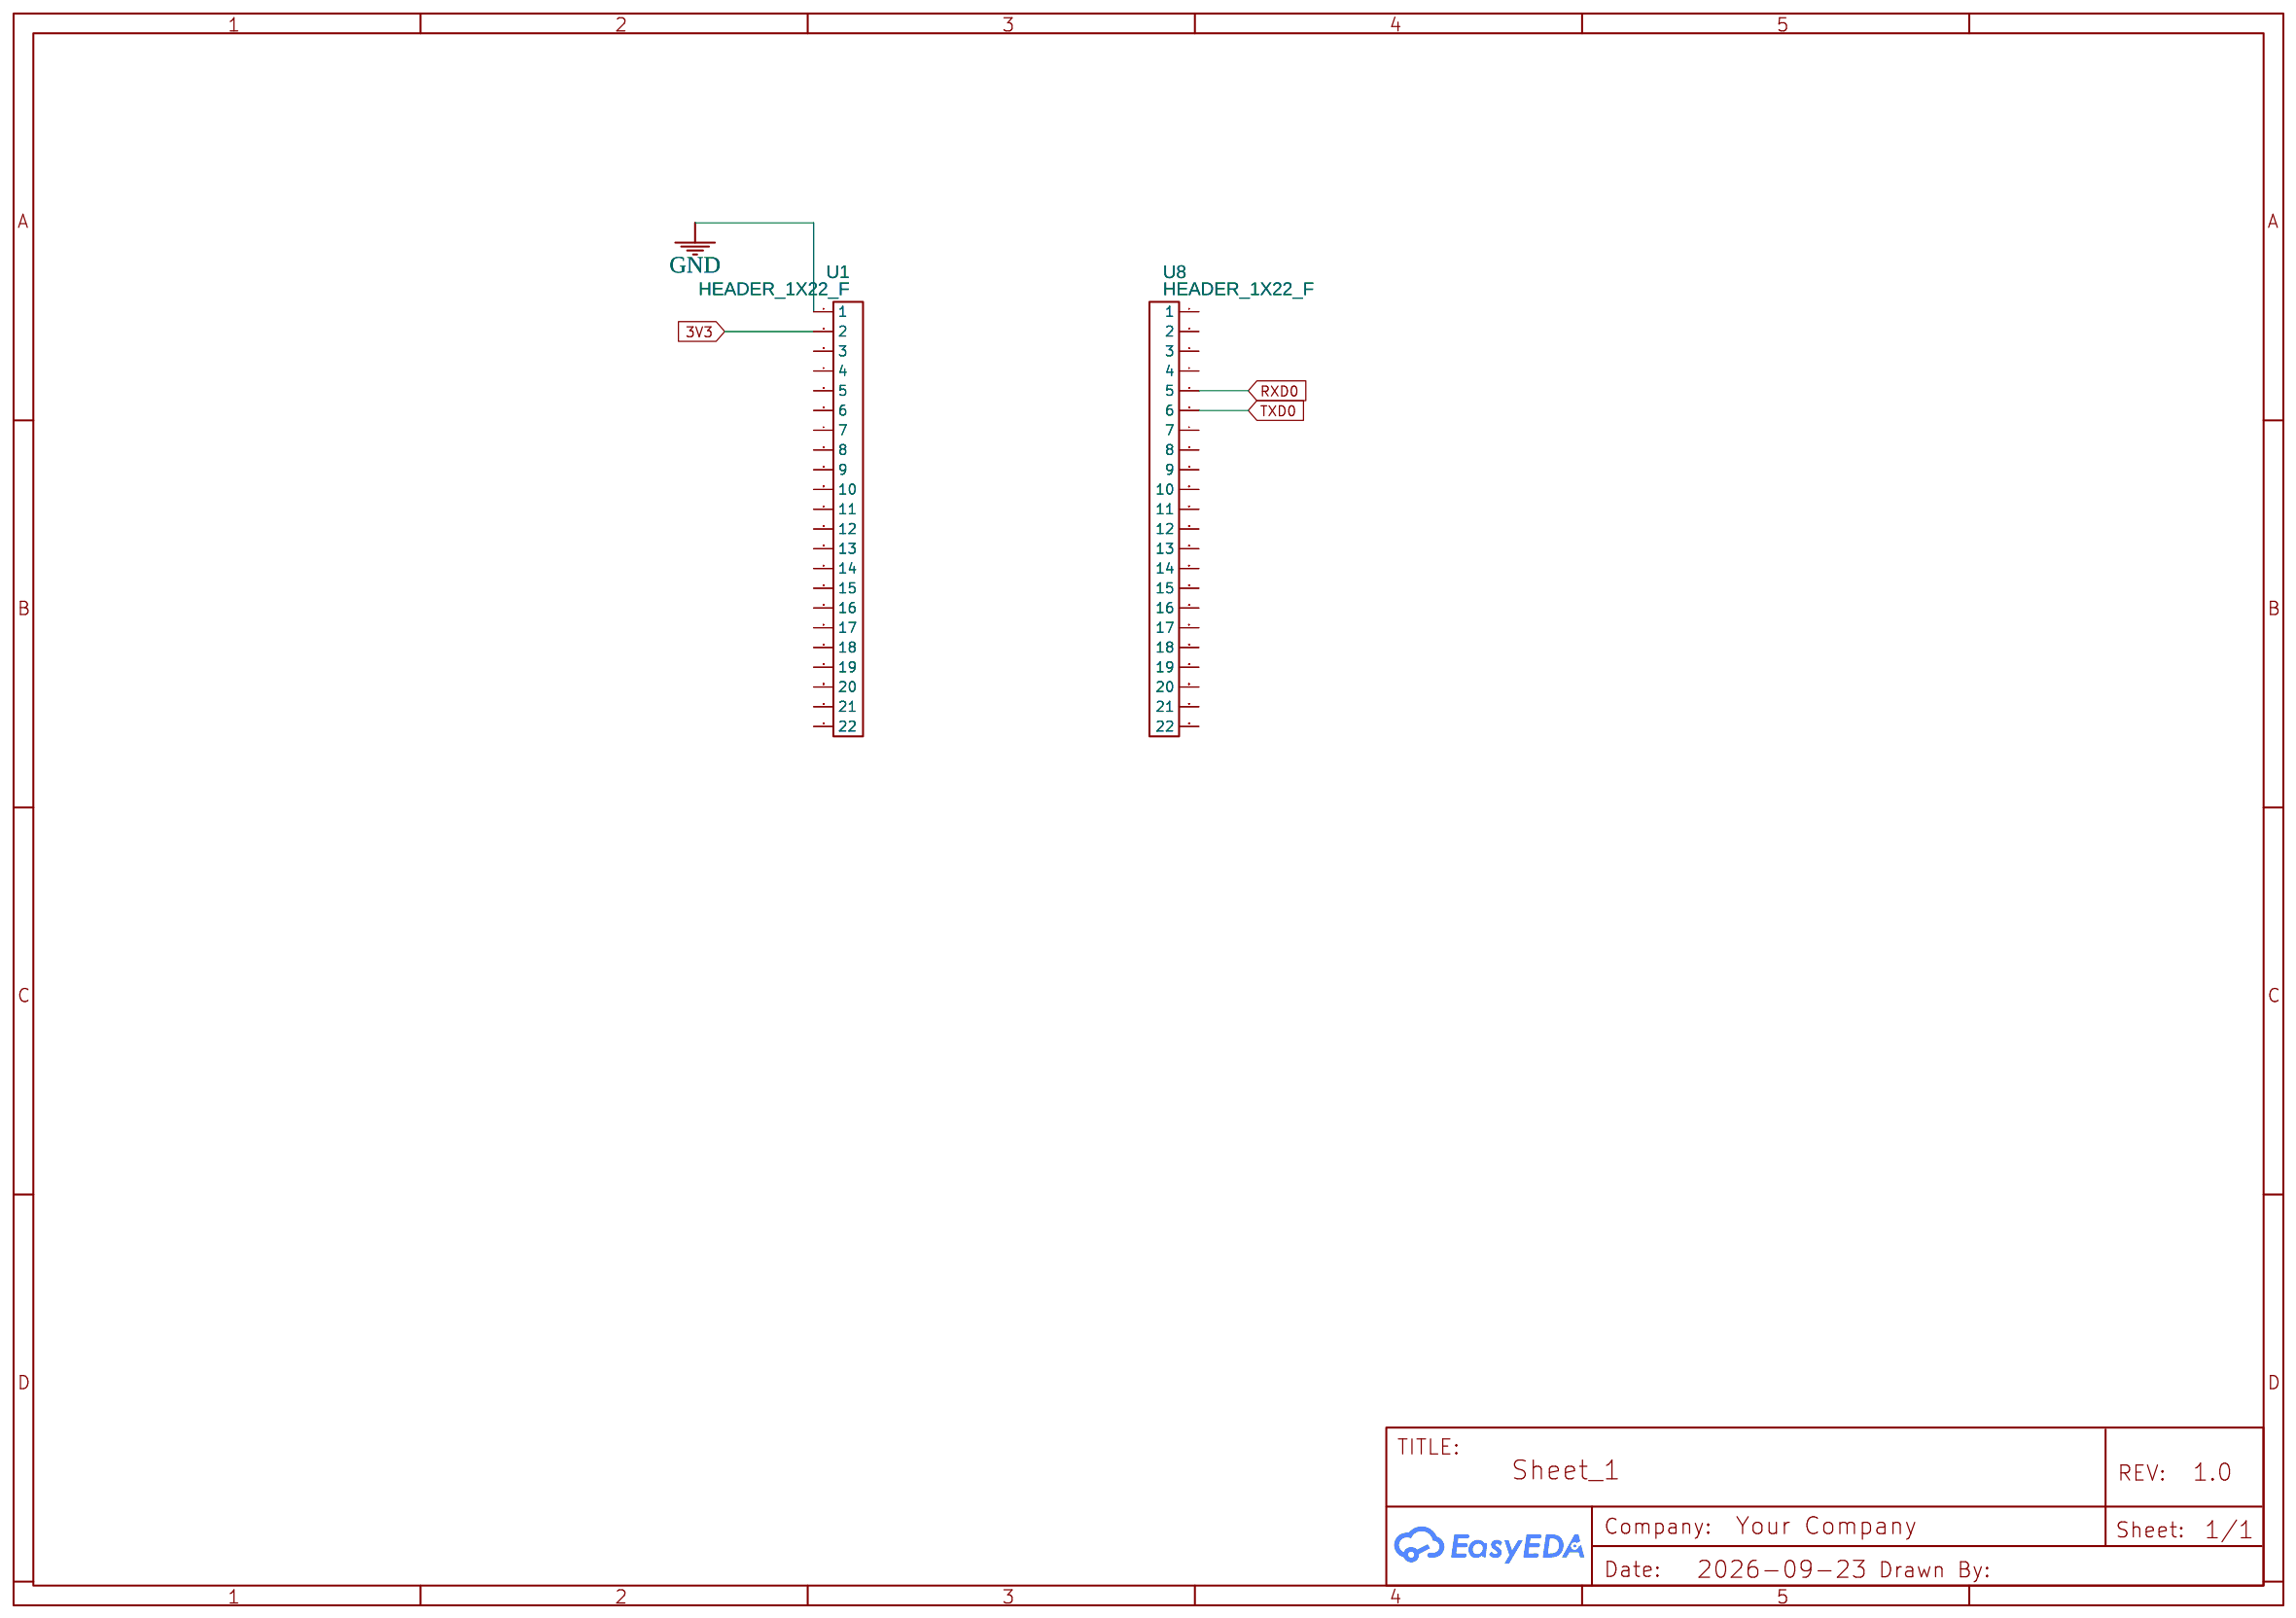
[diagram p8: ESP32-S3-CAM copy]
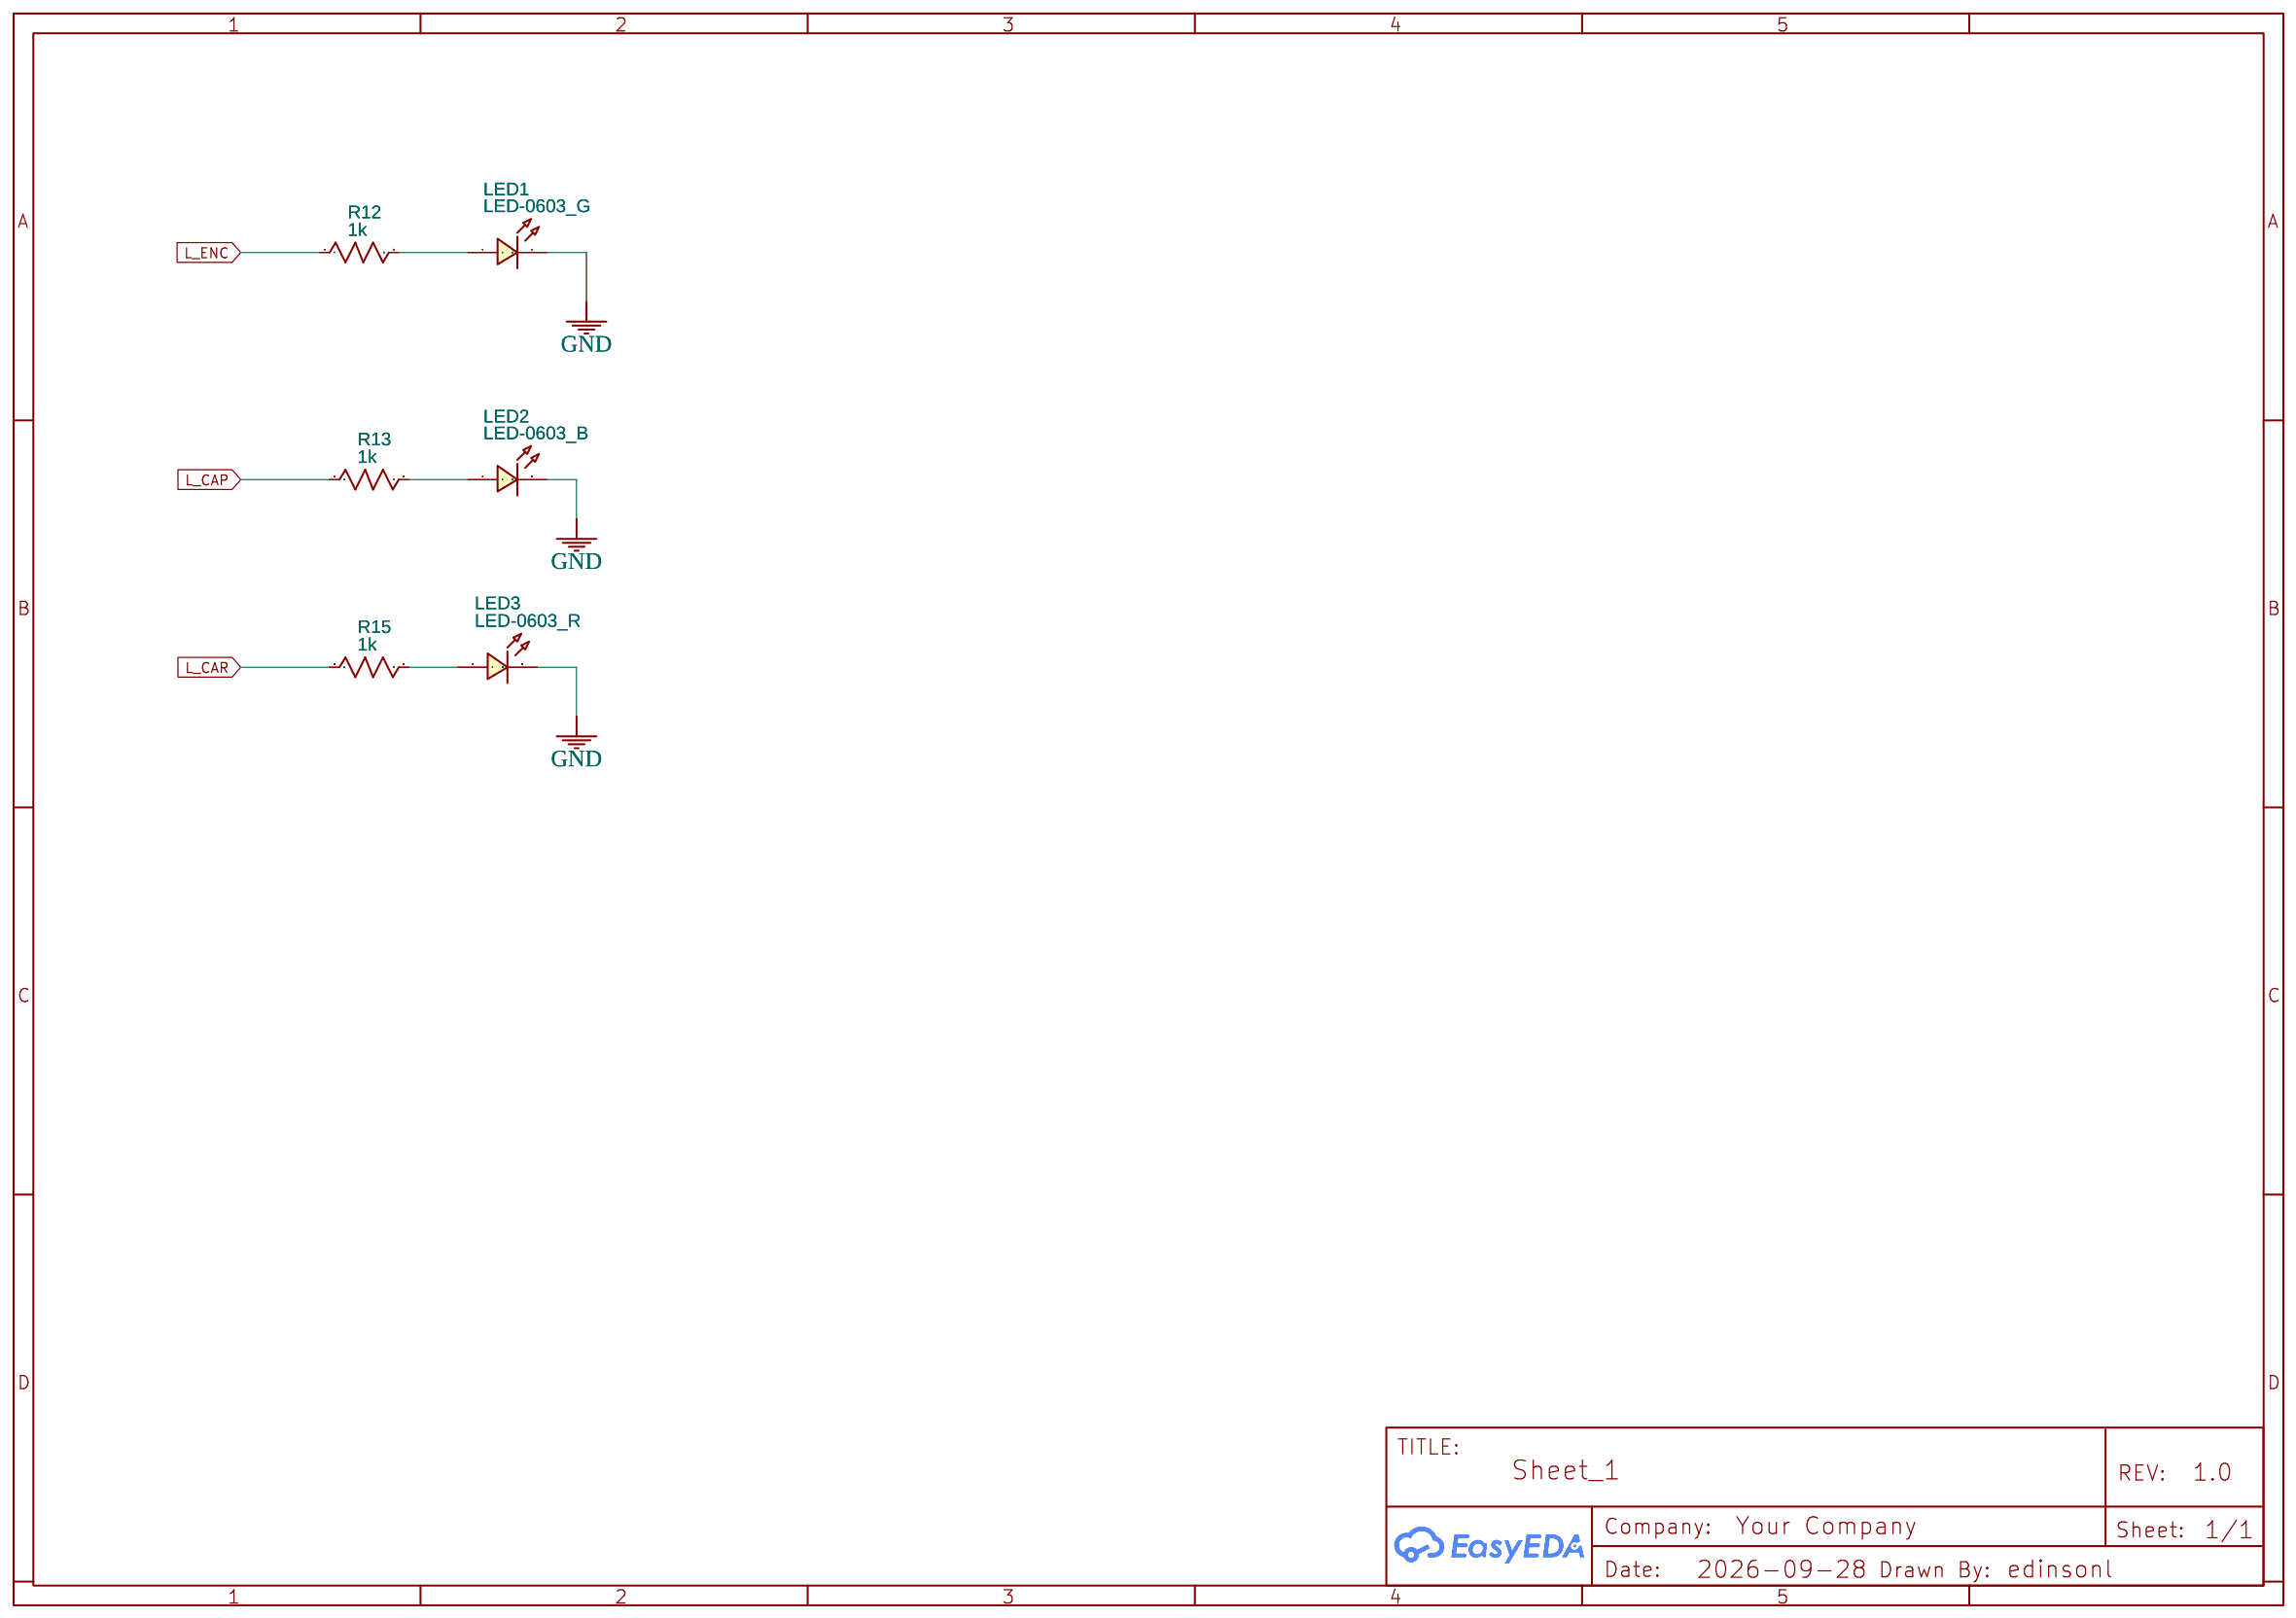
[diagram p9: LEDS]
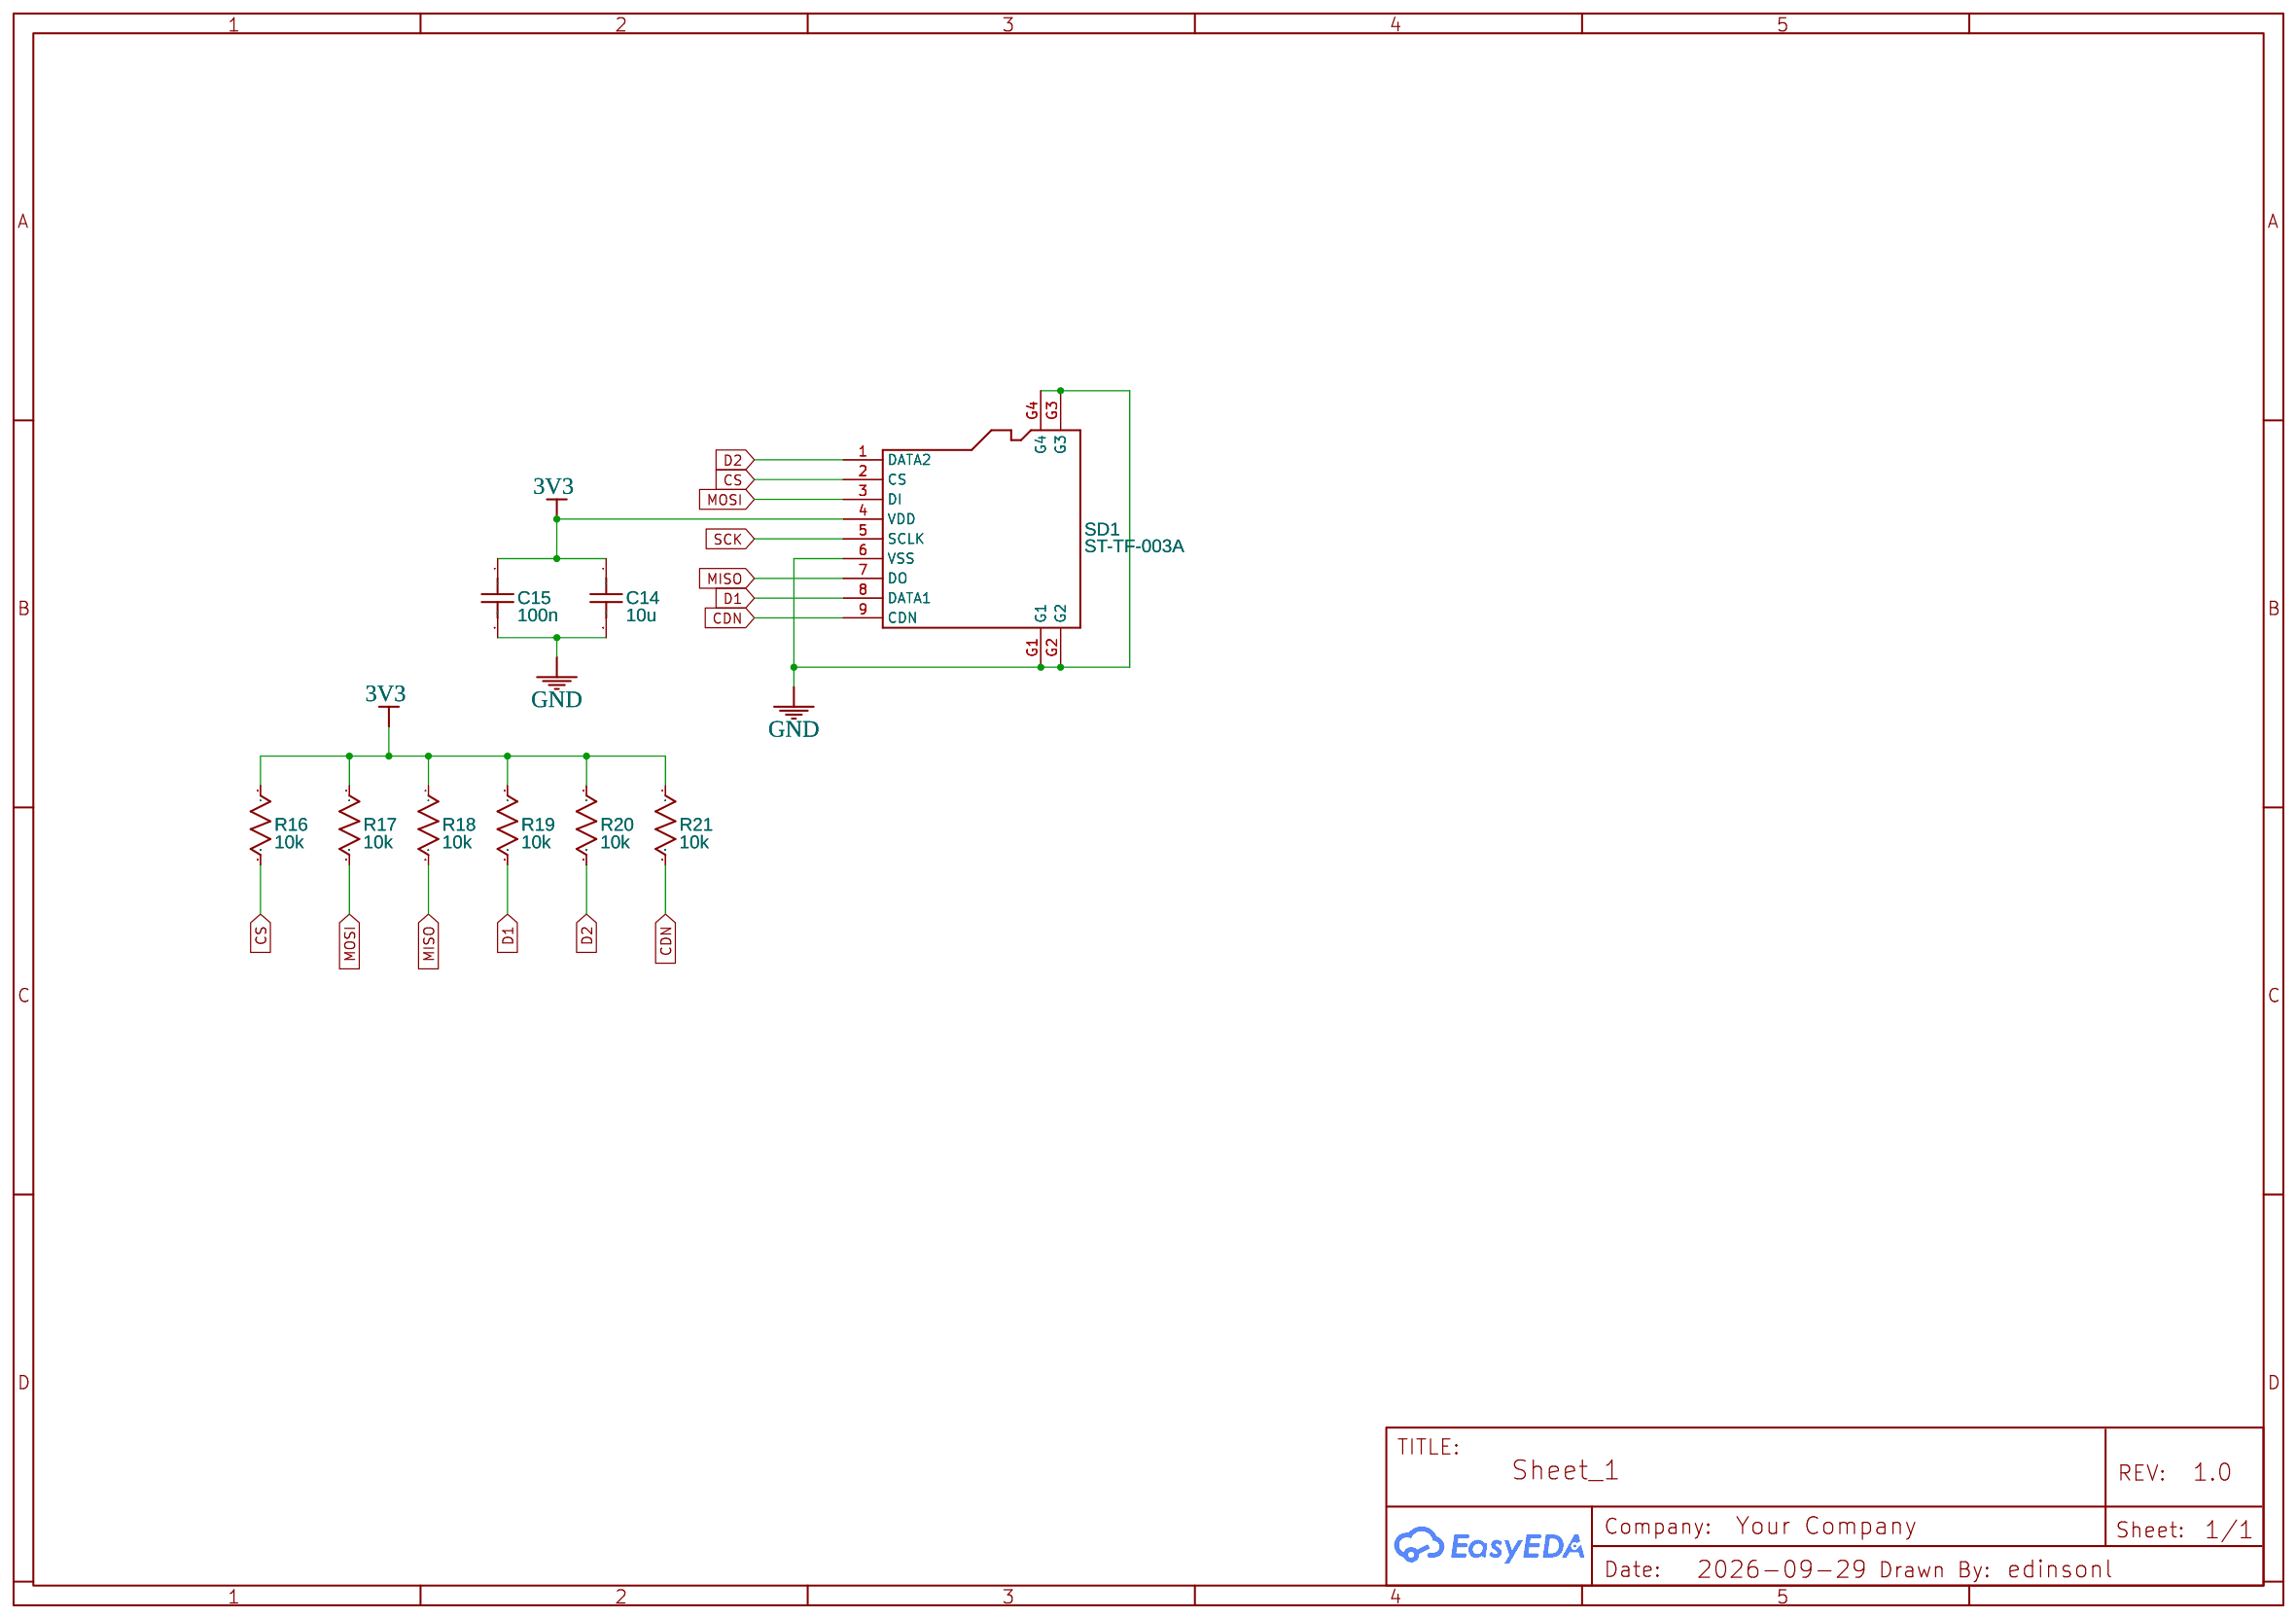
[diagram p10: MicroSD]

(export (version "E")
  (design (tool "Eeschema 10.0.6"))
  (components
    (comp (ref "C1") (value "10uf/25v(20%)") (libsource (lib "") (part "C_0603_US")))
    (comp (ref "C2") (value "0.1uf/50v(10%)") (libsource (lib "") (part "C_0603_US_2")))
    (comp (ref "C3") (value "1uf/16v(10%)") (libsource (lib "") (part "C_0603_US_1")))
    (comp (ref "R1") (value "0(1%)") (libsource (lib "") (part "R_0603_US_1")))
    (comp (ref "R2") (value "10k(1%)") (libsource (lib "") (part "R_0603_US")))
    (comp (ref "U7")
      (value "ESP32-S3-WROOM-1(N16R8)")
      (fields
        (field (name "Manufacturer Part") "ESP32-S3-WROOM-1-N16R8")
        (field (name "Manufacturer") "ESPRESSIF(乐鑫)")
      )
      (libsource (lib "") (part "ESP32-S3-WROOM-1(N16R8)"))
    )
    (comp (ref "Q1")
      (value "BC818-40LT1G")
      (fields (field (name "Manufacturer") "onsemi(安森美)"))
      (libsource (lib "") (part "BC818-40LT1G_1"))
    )
    (comp (ref "Q2")
      (value "BC818-40LT1G")
      (fields (field (name "Manufacturer") "onsemi(安森美)"))
      (libsource (lib "") (part "BC818-40LT1G"))
    )
    (comp (ref "R3") (value "10k(1%)") (libsource (lib "") (part "R_0603_US")))
    (comp (ref "R4") (value "10k(1%)") (libsource (lib "") (part "R_0603_US")))
    (comp (ref "R5") (value "0(1%)") (libsource (lib "") (part "R_0603_US")))
    (comp (ref "R6") (value "0(1%)") (libsource (lib "") (part "R_0603_US")))
    (comp (ref "R7") (value "5.1k(10%)") (libsource (lib "") (part "R_0603_US_1")))
    (comp (ref "R8") (value "5.1k(10%)") (libsource (lib "") (part "R_0603_US_2")))
    (comp (ref "U2")
      (value "CH340C")
      (fields (field (name "Manufacturer") "WCH(南京沁恒)"))
      (libsource (lib "") (part "CH340C"))
    )
    (comp (ref "USB1")
      (value "TYPE-C-16PBS-1MD")
      (fields (field (name "Manufacturer") "CAX(创都)"))
      (libsource (lib "") (part "TYPE-C-16PBS-1MD"))
    )
    (comp (ref "C4") (value "100u(25V)") (libsource (lib "") (part "C_0603_US_1")))
    (comp (ref "C5") (value "100n") (libsource (lib "") (part "C_0603_US_1")))
    (comp (ref "C6") (value "10u(50V)") (libsource (lib "") (part "C_0603_US")))
    (comp (ref "C7") (value "22u(10V)") (libsource (lib "") (part "C_0603_US")))
    (comp (ref "D1") (value "SS34-SMA") (libsource (lib "") (part "SS34-SMA")))
    (comp (ref "F1")
      (value "SMD1206-075C-16V")
      (fields (field (name "Manufacturer") "BNstar(比诺星)"))
      (libsource (lib "") (part "SMD1206-075C-16V"))
    )
    (comp (ref "L1") (value "4.7u(3A)") (libsource (lib "") (part "L0603_US")))
    (comp (ref "Q3")
      (value "AO3401CI-ES")
      (fields (field (name "Manufacturer") "ElecSuper(静芯)"))
      (libsource (lib "") (part "AO3401CI-ES"))
    )
    (comp (ref "R14") (value "10k(10%)") (libsource (lib "") (part "R_0603_US")))
    (comp (ref "U4")
      (value "KF301-5.0-2P")
      (fields (field (name "Manufacturer") "KEFA(科发)"))
      (libsource (lib "") (part "KF301-5.0-2P"))
    )
    (comp (ref "U5")
      (value "SMBJ15A_C5331102")
      (fields (field (name "Manufacturer Part") "SMBJ15A") (field (name "Manufacturer") "MSKSEMI(美森科)"))
      (libsource (lib "") (part "SMBJ15A_C5331102"))
    )
    (comp (ref "U6")
      (value "AP63203WU-7")
      (fields (field (name "Manufacturer") "DIODES(美台)"))
      (libsource (lib "") (part "AP63203WU-7"))
    )
    (comp (ref "PS1")
      (value "M12-S4A-GPLM12-JD")
      (fields (field (name "Manufacturer") "CAZN(正成)"))
      (libsource (lib "") (part "M12-S4A-GPLM12-JD"))
    )
    (comp (ref "U3")
      (value "RS485")
      (fields (field (name "Manufacturer") "GR(国睿)"))
      (libsource (lib "") (part "RS485"))
    )
    (comp (ref "CN1")
      (value "B8B-XH-A")
      (fields (field (name "Manufacturer") "JST"))
      (libsource (lib "") (part "B8B-XH-A"))
    )
    (comp (ref "C8") (value "0.1u") (libsource (lib "") (part "C_0603_US")))
    (comp (ref "R9") (value "10k(1%)") (libsource (lib "") (part "R_0603_US")))
    (comp (ref "R10") (value "10k(1%)") (libsource (lib "") (part "R_0603_US")))
    (comp (ref "R11") (value "1k(1%)") (libsource (lib "") (part "R_0603_US")))
    (comp (ref "U9") (value "CR1220-A") (libsource (lib "") (part "CR1220-A")))
    (comp (ref "U10") (value "DS3231N") (libsource (lib "") (part "DS3231N")))
    (comp (ref "C9") (value "1uf/16v(10%)") (libsource (lib "") (part "C_0603_US")))
    (comp (ref "C10") (value "1uf/16v(10%)") (libsource (lib "") (part "C_0603_US")))
    (comp (ref "C12") (value "1uf/16v(10%)") (libsource (lib "") (part "C_0603_US")))
    (comp (ref "C13") (value "1uf/16v(10%)") (libsource (lib "") (part "C_0603_US")))
    (comp (ref "C16") (value "1uf/16v(10%)") (libsource (lib "") (part "C_0603_US")))
    (comp (ref "S1") (value "NTC013-AA1J-A160T") (libsource (lib "") (part "NTC013-AA1J-A160T")))
    (comp (ref "S2") (value "NTC013-AA1J-A160T") (libsource (lib "") (part "NTC013-AA1J-A160T")))
    (comp (ref "S3") (value "SWITCH-SPST-2TV") (libsource (lib "") (part "SWITCH-SPST-2TV")))
    (comp (ref "S4") (value "NTC013-AA1J-A160T") (libsource (lib "") (part "NTC013-AA1J-A160T_1")))
    (comp (ref "S5") (value "NTC013-AA1J-A160T") (libsource (lib "") (part "NTC013-AA1J-A160T_1")))
    (comp (ref "S6") (value "NTC013-AA1J-A160T") (libsource (lib "") (part "NTC013-AA1J-A160T_1")))
    (comp (ref "H1") (value "HEADER - 2.54_1X4") (libsource (lib "") (part "HEADER - 2.54_1X4")))
    (comp (ref "U1") (value "HEADER_1X22_F") (libsource (lib "") (part "HEADER_1X22_F")))
    (comp (ref "U8") (value "HEADER_1X22_F") (libsource (lib "") (part "HEADER_1X22_F_1")))
    (comp (ref "LED1")
      (value "LED-0603_G")
      (fields
        (field (name "Manufacturer Part") "19-217/R6C-AL1M2VY/3T")
        (field (name "Manufacturer") "EVERLIGHT(台湾亿光)")
      )
      (libsource (lib "") (part "LED-0603_R"))
    )
    (comp (ref "LED2")
      (value "LED-0603_B")
      (fields
        (field (name "Manufacturer Part") "19-217/R6C-AL1M2VY/3T")
        (field (name "Manufacturer") "EVERLIGHT(台湾亿光)")
      )
      (libsource (lib "") (part "LED-0603_R"))
    )
    (comp (ref "LED3")
      (value "LED-0603_R")
      (fields
        (field (name "Manufacturer Part") "19-217/R6C-AL1M2VY/3T")
        (field (name "Manufacturer") "EVERLIGHT(台湾亿光)")
      )
      (libsource (lib "") (part "LED-0603_R"))
    )
    (comp (ref "R12") (value "1k") (libsource (lib "") (part "R_0603_US")))
    (comp (ref "R13") (value "1k") (libsource (lib "") (part "R_0603_US")))
    (comp (ref "R15") (value "1k") (libsource (lib "") (part "R_0603_US")))
    (comp (ref "C14") (value "10u") (libsource (lib "") (part "C_0603_US")))
    (comp (ref "C15") (value "100n") (libsource (lib "") (part "C_0603_US")))
    (comp (ref "R16") (value "10k") (libsource (lib "") (part "R_0603_US")))
    (comp (ref "R17") (value "10k") (libsource (lib "") (part "R_0603_US")))
    (comp (ref "R18") (value "10k") (libsource (lib "") (part "R_0603_US")))
    (comp (ref "R19") (value "10k") (libsource (lib "") (part "R_0603_US")))
    (comp (ref "R20") (value "10k") (libsource (lib "") (part "R_0603_US")))
    (comp (ref "R21") (value "10k") (libsource (lib "") (part "R_0603_US")))
    (comp (ref "SD1") (value "ST-TF-003A") (libsource (lib "") (part "ST-TF-003A")))
  )
  (nets
    (net (code "1") (name "3V3") (class "Default")
      (node (ref "C1") (pin "1") (pinfunction "1_1") (pintype "unspecified"))
      (node (ref "C14") (pin "1") (pinfunction "1_1") (pintype "unspecified"))
      (node (ref "C15") (pin "1") (pinfunction "1_1") (pintype "unspecified"))
      (node (ref "C2") (pin "2") (pinfunction "2_2") (pintype "unspecified"))
      (node (ref "C7") (pin "1") (pinfunction "1_1") (pintype "unspecified"))
      (node (ref "C8") (pin "1") (pinfunction "1_1") (pintype "unspecified"))
      (node (ref "CN1") (pin "1") (pinfunction "1_1") (pintype "unspecified"))
      (node (ref "H1") (pin "4") (pinfunction "4_4") (pintype "unspecified"))
      (node (ref "L1") (pin "2") (pinfunction "2_2") (pintype "unspecified"))
      (node (ref "R1") (pin "1") (pinfunction "1_1") (pintype "unspecified"))
      (node (ref "R10") (pin "1") (pinfunction "1_1") (pintype "unspecified"))
      (node (ref "R11") (pin "1") (pinfunction "1_1") (pintype "unspecified"))
      (node (ref "R16") (pin "1") (pinfunction "1_1") (pintype "unspecified"))
      (node (ref "R17") (pin "1") (pinfunction "1_1") (pintype "unspecified"))
      (node (ref "R18") (pin "1") (pinfunction "1_1") (pintype "unspecified"))
      (node (ref "R19") (pin "1") (pinfunction "1_1") (pintype "unspecified"))
      (node (ref "R2") (pin "2") (pinfunction "2_2") (pintype "unspecified"))
      (node (ref "R20") (pin "1") (pinfunction "1_1") (pintype "unspecified"))
      (node (ref "R21") (pin "1") (pinfunction "1_1") (pintype "unspecified"))
      (node (ref "R9") (pin "1") (pinfunction "1_1") (pintype "unspecified"))
      (node (ref "SD1") (pin "4") (pinfunction "VDD_4") (pintype "unspecified"))
      (node (ref "U1") (pin "2") (pinfunction "2_2") (pintype "unspecified"))
      (node (ref "U10") (pin "2") (pinfunction "VCC_2") (pintype "unspecified"))
      (node (ref "U2") (pin "16") (pinfunction "VCC_16") (pintype "unspecified"))
      (node (ref "U2") (pin "4") (pinfunction "V3_4") (pintype "unspecified"))
      (node (ref "U3") (pin "8") (pinfunction "VCC_8") (pintype "unspecified"))
      (node (ref "U6") (pin "1") (pinfunction "FB_1") (pintype "unspecified"))
    )
    (net (code "2") (name "12V") (class "Default")
      (node (ref "C4") (pin "1") (pinfunction "1_1") (pintype "unspecified"))
      (node (ref "C6") (pin "1") (pinfunction "1_1") (pintype "unspecified"))
      (node (ref "D1") (pin "2") (pinfunction "2_2") (pintype "unspecified"))
      (node (ref "PS1") (pin "1") (pinfunction "1_1") (pintype "unspecified"))
      (node (ref "Q3") (pin "2") (pinfunction "S_2") (pintype "unspecified"))
      (node (ref "Q3") (pin "3") (pinfunction "D_3") (pintype "unspecified"))
      (node (ref "R14") (pin "1") (pinfunction "1_1") (pintype "unspecified"))
      (node (ref "S3") (pin "1") (pinfunction "O_1") (pintype "unspecified"))
      (node (ref "U5") (pin "1") (pinfunction "C_1") (pintype "unspecified"))
      (node (ref "U6") (pin "2") (pinfunction "EN_2") (pintype "unspecified"))
      (node (ref "U6") (pin "3") (pinfunction "VIN_3") (pintype "unspecified"))
    )
    (net (code "3") (name "32kHz") (class "Default")
      (node (ref "U10") (pin "1") (pinfunction "32KHZ_1") (pintype "unspecified"))
    )
    (net (code "4") (name "Boot") (class "Default")
      (node (ref "C9") (pin "2") (pinfunction "2_2") (pintype "unspecified"))
      (node (ref "R6") (pin "2") (pinfunction "2_2") (pintype "unspecified"))
      (node (ref "S2") (pin "3") (pinfunction "COM_2_3") (pintype "bidirectional"))
      (node (ref "U7") (pin "27") (pinfunction "IO0_27") (pintype "unspecified"))
    )
    (net (code "5") (name "CAP") (class "Default")
      (node (ref "C12") (pin "2") (pinfunction "2_2") (pintype "unspecified"))
      (node (ref "S4") (pin "3") (pinfunction "COM_2_3") (pintype "bidirectional"))
      (node (ref "U7") (pin "4") (pinfunction "IO4_4") (pintype "unspecified"))
    )
    (net (code "6") (name "CAR") (class "Default")
      (node (ref "C13") (pin "2") (pinfunction "2_2") (pintype "unspecified"))
      (node (ref "S5") (pin "3") (pinfunction "COM_2_3") (pintype "bidirectional"))
      (node (ref "U7") (pin "5") (pinfunction "IO5_5") (pintype "unspecified"))
    )
    (net (code "7") (name "CDN") (class "Default")
      (node (ref "R21") (pin "2") (pinfunction "2_2") (pintype "unspecified"))
      (node (ref "SD1") (pin "9") (pinfunction "CDN_9") (pintype "unspecified"))
      (node (ref "U7") (pin "22") (pinfunction "IO14_22") (pintype "unspecified"))
    )
    (net (code "8") (name "CS") (class "Default")
      (node (ref "R16") (pin "2") (pinfunction "2_2") (pintype "unspecified"))
      (node (ref "SD1") (pin "2") (pinfunction "CS_2") (pintype "unspecified"))
      (node (ref "U7") (pin "18") (pinfunction "IO10_18") (pintype "unspecified"))
    )
    (net (code "9") (name "D1") (class "Default")
      (node (ref "R19") (pin "2") (pinfunction "2_2") (pintype "unspecified"))
      (node (ref "SD1") (pin "8") (pinfunction "DATA1_8") (pintype "unspecified"))
    )
    (net (code "10") (name "D2") (class "Default")
      (node (ref "R20") (pin "2") (pinfunction "2_2") (pintype "unspecified"))
      (node (ref "SD1") (pin "1") (pinfunction "DATA2_1") (pintype "unspecified"))
    )
    (net (code "11") (name "DTR") (class "Default")
      (node (ref "Q2") (pin "2") (pinfunction "E_2") (pintype "input"))
      (node (ref "R3") (pin "1") (pinfunction "1_1") (pintype "unspecified"))
      (node (ref "U2") (pin "13") (pinfunction "DTR#_13") (pintype "unspecified"))
    )
    (net (code "12") (name "EN") (class "Default")
      (node (ref "C10") (pin "2") (pinfunction "2_2") (pintype "unspecified"))
      (node (ref "C3") (pin "2") (pinfunction "2_2") (pintype "unspecified"))
      (node (ref "R2") (pin "1") (pinfunction "1_1") (pintype "unspecified"))
      (node (ref "R5") (pin "2") (pinfunction "2_2") (pintype "unspecified"))
      (node (ref "S1") (pin "3") (pinfunction "COM_2_3") (pintype "bidirectional"))
      (node (ref "U7") (pin "3") (pinfunction "EN_3") (pintype "unspecified"))
    )
    (net (code "13") (name "EPD_BUSY") (class "Default")
      (node (ref "CN1") (pin "8") (pinfunction "8_8") (pintype "unspecified"))
      (node (ref "U7") (pin "31") (pinfunction "IO38_31") (pintype "unspecified"))
    )
    (net (code "14") (name "EPD_CS") (class "Default")
      (node (ref "CN1") (pin "5") (pinfunction "5_5") (pintype "unspecified"))
      (node (ref "U7") (pin "23") (pinfunction "IO21_23") (pintype "unspecified"))
    )
    (net (code "15") (name "EPD_DC") (class "Default")
      (node (ref "CN1") (pin "6") (pinfunction "6_6") (pintype "unspecified"))
      (node (ref "U7") (pin "24") (pinfunction "IO47_24") (pintype "unspecified"))
    )
    (net (code "16") (name "EPD_RST") (class "Default")
      (node (ref "CN1") (pin "7") (pinfunction "7_7") (pintype "unspecified"))
      (node (ref "U7") (pin "25") (pinfunction "IO48_25") (pintype "unspecified"))
    )
    (net (code "17") (name "ESP-3V3") (class "Default")
      (node (ref "R1") (pin "2") (pinfunction "2_2") (pintype "unspecified"))
      (node (ref "U7") (pin "2") (pinfunction "3V3_2") (pintype "unspecified"))
    )
    (net (code "18") (name "GND") (class "Default")
      (node (ref "C1") (pin "2") (pinfunction "2_2") (pintype "unspecified"))
      (node (ref "C10") (pin "1") (pinfunction "1_1") (pintype "unspecified"))
      (node (ref "C12") (pin "1") (pinfunction "1_1") (pintype "unspecified"))
      (node (ref "C13") (pin "1") (pinfunction "1_1") (pintype "unspecified"))
      (node (ref "C14") (pin "2") (pinfunction "2_2") (pintype "unspecified"))
      (node (ref "C15") (pin "2") (pinfunction "2_2") (pintype "unspecified"))
      (node (ref "C16") (pin "1") (pinfunction "1_1") (pintype "unspecified"))
      (node (ref "C2") (pin "1") (pinfunction "1_1") (pintype "unspecified"))
      (node (ref "C3") (pin "1") (pinfunction "1_1") (pintype "unspecified"))
      (node (ref "C4") (pin "2") (pinfunction "2_2") (pintype "unspecified"))
      (node (ref "C6") (pin "2") (pinfunction "2_2") (pintype "unspecified"))
      (node (ref "C7") (pin "2") (pinfunction "2_2") (pintype "unspecified"))
      (node (ref "C8") (pin "2") (pinfunction "2_2") (pintype "unspecified"))
      (node (ref "C9") (pin "1") (pinfunction "1_1") (pintype "unspecified"))
      (node (ref "CN1") (pin "2") (pinfunction "2_2") (pintype "unspecified"))
      (node (ref "H1") (pin "1") (pinfunction "1_1") (pintype "unspecified"))
      (node (ref "LED1") (pin "2") (pinfunction "2_2") (pintype "unspecified"))
      (node (ref "LED2") (pin "2") (pinfunction "2_2") (pintype "unspecified"))
      (node (ref "LED3") (pin "2") (pinfunction "2_2") (pintype "unspecified"))
      (node (ref "PS1") (pin "3") (pinfunction "3_3") (pintype "unspecified"))
      (node (ref "R7") (pin "2") (pinfunction "2_2") (pintype "unspecified"))
      (node (ref "R8") (pin "1") (pinfunction "1_1") (pintype "unspecified"))
      (node (ref "S1") (pin "1") (pinfunction "NO_1_1") (pintype "bidirectional"))
      (node (ref "S2") (pin "1") (pinfunction "NO_1_1") (pintype "bidirectional"))
      (node (ref "S3") (pin "2") (pinfunction "P_2") (pintype "unspecified"))
      (node (ref "S4") (pin "1") (pinfunction "NO_1_1") (pintype "bidirectional"))
      (node (ref "S5") (pin "1") (pinfunction "NO_1_1") (pintype "bidirectional"))
      (node (ref "S6") (pin "1") (pinfunction "NO_1_1") (pintype "bidirectional"))
      (node (ref "SD1") (pin "6") (pinfunction "VSS_6") (pintype "unspecified"))
      (node (ref "SD1") (pin "G1") (pinfunction "G1_G1") (pintype "unspecified"))
      (node (ref "SD1") (pin "G2") (pinfunction "G2_G2") (pintype "unspecified"))
      (node (ref "SD1") (pin "G3") (pinfunction "G3_G3") (pintype "unspecified"))
      (node (ref "SD1") (pin "G4") (pinfunction "G4_G4") (pintype "unspecified"))
      (node (ref "U1") (pin "1") (pinfunction "1_1") (pintype "unspecified"))
      (node (ref "U10") (pin "10") (pinfunction "N.C._10") (pintype "unspecified"))
      (node (ref "U10") (pin "11") (pinfunction "N.C._11") (pintype "unspecified"))
      (node (ref "U10") (pin "12") (pinfunction "N.C._12") (pintype "unspecified"))
      (node (ref "U10") (pin "13") (pinfunction "GND_13") (pintype "unspecified"))
      (node (ref "U10") (pin "5") (pinfunction "N.C._5") (pintype "unspecified"))
      (node (ref "U10") (pin "6") (pinfunction "N.C._6") (pintype "unspecified"))
      (node (ref "U10") (pin "7") (pinfunction "N.C._7") (pintype "unspecified"))
      (node (ref "U10") (pin "8") (pinfunction "N.C._8") (pintype "unspecified"))
      (node (ref "U10") (pin "9") (pinfunction "N.C._9") (pintype "unspecified"))
      (node (ref "U2") (pin "1") (pinfunction "GND_1") (pintype "unspecified"))
      (node (ref "U3") (pin "5") (pinfunction "VO1_5") (pintype "unspecified"))
      (node (ref "U4") (pin "2") (pinfunction "2_2") (pintype "unspecified"))
      (node (ref "U5") (pin "2") (pinfunction "A_2") (pintype "unspecified"))
      (node (ref "U6") (pin "4") (pinfunction "GND_4") (pintype "unspecified"))
      (node (ref "U7") (pin "1") (pinfunction "GND_1") (pintype "unspecified"))
      (node (ref "U7") (pin "40") (pinfunction "GND_40") (pintype "unspecified"))
      (node (ref "U7") (pin "41") (pinfunction "GND_41") (pintype "unspecified"))
      (node (ref "U9") (pin "2") (pinfunction "2_2") (pintype "input"))
      (node (ref "USB1") (pin "1") (pinfunction "EH_1") (pintype "unspecified"))
      (node (ref "USB1") (pin "2") (pinfunction "EH_2") (pintype "unspecified"))
      (node (ref "USB1") (pin "3") (pinfunction "EH_3") (pintype "unspecified"))
      (node (ref "USB1") (pin "4") (pinfunction "EH_4") (pintype "unspecified"))
      (node (ref "USB1") (pin "A1B12") (pinfunction "GND_A1B12") (pintype "unspecified"))
      (node (ref "USB1") (pin "B1A12") (pinfunction "GND_B1A12") (pintype "unspecified"))
    )
    (net (code "19") (name "IO16") (class "Default")
      (node (ref "U3") (pin "2") (pinfunction "RE#_2") (pintype "unspecified"))
      (node (ref "U3") (pin "3") (pinfunction "DE_3") (pintype "unspecified"))
      (node (ref "U7") (pin "9") (pinfunction "IO16_9") (pintype "unspecified"))
    )
    (net (code "20") (name "IO17") (class "Default")
      (node (ref "U3") (pin "4") (pinfunction "DI_4") (pintype "unspecified"))
      (node (ref "U7") (pin "10") (pinfunction "IO17_10") (pintype "unspecified"))
    )
    (net (code "21") (name "IO18") (class "Default")
      (node (ref "U3") (pin "1") (pinfunction "R0_1") (pintype "unspecified"))
      (node (ref "U7") (pin "11") (pinfunction "IO18_11") (pintype "unspecified"))
    )
    (net (code "22") (name "L_CAP") (class "Default")
      (node (ref "R13") (pin "1") (pinfunction "1_1") (pintype "unspecified"))
      (node (ref "U7") (pin "7") (pinfunction "IO7_7") (pintype "unspecified"))
    )
    (net (code "23") (name "L_CAR") (class "Default")
      (node (ref "R15") (pin "1") (pinfunction "1_1") (pintype "unspecified"))
      (node (ref "U7") (pin "8") (pinfunction "IO15_8") (pintype "unspecified"))
    )
    (net (code "24") (name "L_ENC") (class "Default")
      (node (ref "R12") (pin "1") (pinfunction "1_1") (pintype "unspecified"))
      (node (ref "U7") (pin "6") (pinfunction "IO6_6") (pintype "unspecified"))
    )
    (net (code "25") (name "MISO") (class "Default")
      (node (ref "R18") (pin "2") (pinfunction "2_2") (pintype "unspecified"))
      (node (ref "SD1") (pin "7") (pinfunction "DO_7") (pintype "unspecified"))
      (node (ref "U7") (pin "21") (pinfunction "IO13_21") (pintype "unspecified"))
    )
    (net (code "26") (name "MOSI") (class "Default")
      (node (ref "CN1") (pin "3") (pinfunction "3_3") (pintype "unspecified"))
      (node (ref "R17") (pin "2") (pinfunction "2_2") (pintype "unspecified"))
      (node (ref "SD1") (pin "3") (pinfunction "DI_3") (pintype "unspecified"))
      (node (ref "U7") (pin "19") (pinfunction "IO11_19") (pintype "unspecified"))
    )
    (net (code "27") (name "Net-(D1-Pad1)") (class "Default")
      (node (ref "D1") (pin "1") (pinfunction "1_1") (pintype "unspecified"))
      (node (ref "F1") (pin "2") (pinfunction "2_2") (pintype "unspecified"))
    )
    (net (code "28") (name "Net-(F1-Pad1)") (class "Default")
      (node (ref "F1") (pin "1") (pinfunction "1_1") (pintype "unspecified"))
      (node (ref "U4") (pin "1") (pinfunction "1_1") (pintype "unspecified"))
    )
    (net (code "29") (name "Net-(LED1-Pad1)") (class "Default")
      (node (ref "LED1") (pin "1") (pinfunction "1_1") (pintype "unspecified"))
      (node (ref "R12") (pin "2") (pinfunction "2_2") (pintype "unspecified"))
    )
    (net (code "30") (name "Net-(LED2-Pad1)") (class "Default")
      (node (ref "LED2") (pin "1") (pinfunction "1_1") (pintype "unspecified"))
      (node (ref "R13") (pin "2") (pinfunction "2_2") (pintype "unspecified"))
    )
    (net (code "31") (name "Net-(LED3-Pad1)") (class "Default")
      (node (ref "LED3") (pin "1") (pinfunction "1_1") (pintype "unspecified"))
      (node (ref "R15") (pin "2") (pinfunction "2_2") (pintype "unspecified"))
    )
    (net (code "32") (name "Net-(Q1-B)") (class "Default")
      (node (ref "Q1") (pin "1") (pinfunction "B_1") (pintype "input"))
      (node (ref "R3") (pin "2") (pinfunction "2_2") (pintype "unspecified"))
    )
    (net (code "33") (name "Net-(Q1-C)") (class "Default")
      (node (ref "Q1") (pin "3") (pinfunction "C_3") (pintype "input"))
      (node (ref "R5") (pin "1") (pinfunction "1_1") (pintype "unspecified"))
    )
    (net (code "34") (name "Net-(Q2-B)") (class "Default")
      (node (ref "Q2") (pin "1") (pinfunction "B_1") (pintype "input"))
      (node (ref "R4") (pin "2") (pinfunction "2_2") (pintype "unspecified"))
    )
    (net (code "35") (name "Net-(Q2-C)") (class "Default")
      (node (ref "Q2") (pin "3") (pinfunction "C_3") (pintype "input"))
      (node (ref "R6") (pin "1") (pinfunction "1_1") (pintype "unspecified"))
    )
    (net (code "36") (name "Net-(Q3-G)") (class "Default")
      (node (ref "Q3") (pin "1") (pinfunction "G_1") (pintype "unspecified"))
      (node (ref "R14") (pin "2") (pinfunction "2_2") (pintype "unspecified"))
    )
    (net (code "37") (name "Net-(U3-A)") (class "Default")
      (node (ref "PS1") (pin "2") (pinfunction "2_2") (pintype "unspecified"))
      (node (ref "U3") (pin "6") (pinfunction "A_6") (pintype "unspecified"))
    )
    (net (code "38") (name "Net-(U3-B)") (class "Default")
      (node (ref "PS1") (pin "4") (pinfunction "4_4") (pintype "unspecified"))
      (node (ref "U3") (pin "7") (pinfunction "B_7") (pintype "unspecified"))
    )
    (net (code "39") (name "Net-(U6-BST)") (class "Default")
      (node (ref "C5") (pin "1") (pinfunction "1_1") (pintype "unspecified"))
      (node (ref "U6") (pin "6") (pinfunction "BST_6") (pintype "unspecified"))
    )
    (net (code "40") (name "Net-(U6-SW)") (class "Default")
      (node (ref "C5") (pin "2") (pinfunction "2_2") (pintype "unspecified"))
      (node (ref "L1") (pin "1") (pinfunction "1_1") (pintype "unspecified"))
      (node (ref "U6") (pin "5") (pinfunction "SW_5") (pintype "unspecified"))
    )
    (net (code "41") (name "Net-(U10-INT{slash}SQW)") (class "Default")
      (node (ref "R11") (pin "2") (pinfunction "2_2") (pintype "unspecified"))
      (node (ref "U10") (pin "3") (pinfunction "INT/SQW_3") (pintype "unspecified"))
    )
    (net (code "42") (name "Net-(U10-VBAT)") (class "Default")
      (node (ref "U10") (pin "14") (pinfunction "VBAT_14") (pintype "unspecified"))
      (node (ref "U9") (pin "1") (pinfunction "1_1") (pintype "input"))
    )
    (net (code "43") (name "Net-(USB1-CC1)") (class "Default")
      (node (ref "R7") (pin "1") (pinfunction "1_1") (pintype "unspecified"))
      (node (ref "USB1") (pin "A5") (pinfunction "CC1_A5") (pintype "unspecified"))
    )
    (net (code "44") (name "Net-(USB1-CC2)") (class "Default")
      (node (ref "R8") (pin "2") (pinfunction "2_2") (pintype "unspecified"))
      (node (ref "USB1") (pin "B5") (pinfunction "CC2_B5") (pintype "unspecified"))
    )
    (net (code "45") (name "RESET_RTC") (class "Default")
      (node (ref "C16") (pin "2") (pinfunction "2_2") (pintype "unspecified"))
      (node (ref "S6") (pin "3") (pinfunction "COM_2_3") (pintype "bidirectional"))
      (node (ref "U10") (pin "4") (pinfunction "RST#_4") (pintype "unspecified"))
    )
    (net (code "46") (name "RTS") (class "Default")
      (node (ref "Q1") (pin "2") (pinfunction "E_2") (pintype "input"))
      (node (ref "R4") (pin "1") (pinfunction "1_1") (pintype "unspecified"))
      (node (ref "U2") (pin "14") (pinfunction "RTS#_14") (pintype "unspecified"))
    )
    (net (code "47") (name "RXD0") (class "Default")
      (node (ref "U2") (pin "2") (pinfunction "TXD_2") (pintype "unspecified"))
      (node (ref "U7") (pin "36") (pinfunction "RXD0_36") (pintype "unspecified"))
      (node (ref "U8") (pin "5") (pinfunction "5_5") (pintype "unspecified"))
    )
    (net (code "48") (name "RX_GPS") (class "Default")
      (node (ref "H1") (pin "3") (pinfunction "3_3") (pintype "unspecified"))
      (node (ref "U7") (pin "12") (pinfunction "IO8_12") (pintype "unspecified"))
    )
    (net (code "49") (name "SCK") (class "Default")
      (node (ref "CN1") (pin "4") (pinfunction "4_4") (pintype "unspecified"))
      (node (ref "SD1") (pin "5") (pinfunction "SCLK_5") (pintype "unspecified"))
      (node (ref "U7") (pin "20") (pinfunction "IO12_20") (pintype "unspecified"))
    )
    (net (code "50") (name "SCL") (class "Default")
      (node (ref "R9") (pin "2") (pinfunction "2_2") (pintype "unspecified"))
      (node (ref "U10") (pin "16") (pinfunction "SCL_16") (pintype "unspecified"))
      (node (ref "U7") (pin "38") (pinfunction "IO2_38") (pintype "unspecified"))
    )
    (net (code "51") (name "SDA") (class "Default")
      (node (ref "R10") (pin "2") (pinfunction "2_2") (pintype "unspecified"))
      (node (ref "U10") (pin "15") (pinfunction "SDA_15") (pintype "unspecified"))
      (node (ref "U7") (pin "39") (pinfunction "IO1_39") (pintype "unspecified"))
    )
    (net (code "52") (name "TXD0") (class "Default")
      (node (ref "U2") (pin "3") (pinfunction "RXD_3") (pintype "unspecified"))
      (node (ref "U7") (pin "37") (pinfunction "TXD0_37") (pintype "unspecified"))
      (node (ref "U8") (pin "6") (pinfunction "6_6") (pintype "unspecified"))
    )
    (net (code "53") (name "TX_GPS") (class "Default")
      (node (ref "H1") (pin "2") (pinfunction "2_2") (pintype "unspecified"))
      (node (ref "U7") (pin "17") (pinfunction "IO9_17") (pintype "unspecified"))
    )
    (net (code "54") (name "USB_DN") (class "Default")
      (node (ref "U2") (pin "6") (pinfunction "D-_6") (pintype "unspecified"))
      (node (ref "USB1") (pin "A7") (pinfunction "DN1_A7") (pintype "unspecified"))
      (node (ref "USB1") (pin "B7") (pinfunction "DN2_B7") (pintype "unspecified"))
    )
    (net (code "55") (name "USB_DP") (class "Default")
      (node (ref "U2") (pin "5") (pinfunction "D+_5") (pintype "unspecified"))
      (node (ref "USB1") (pin "A6") (pinfunction "DP1_A6") (pintype "unspecified"))
      (node (ref "USB1") (pin "B6") (pinfunction "DP2_B6") (pintype "unspecified"))
    )
    (net (code "56") (name "VBUS") (class "Default")
      (node (ref "USB1") (pin "A4B9") (pinfunction "VBUS_A4B9") (pintype "unspecified"))
      (node (ref "USB1") (pin "B4A9") (pinfunction "VBUS_B4A9") (pintype "unspecified"))
    )
    (net (code "57") (name "unconnected-(PS1-Pad5)") (class "Default")
      (node (ref "PS1") (pin "5") (pinfunction "5_5") (pintype "unspecified+no_connect"))
    )
    (net (code "58") (name "unconnected-(S1-COM_1-Pad2)") (class "Default")
      (node (ref "S1") (pin "2") (pinfunction "COM_1_2") (pintype "bidirectional+no_connect"))
    )
    (net (code "59") (name "unconnected-(S1-NO_2-Pad4)") (class "Default")
      (node (ref "S1") (pin "4") (pinfunction "NO_2_4") (pintype "bidirectional+no_connect"))
    )
    (net (code "60") (name "unconnected-(S2-COM_1-Pad2)") (class "Default")
      (node (ref "S2") (pin "2") (pinfunction "COM_1_2") (pintype "bidirectional+no_connect"))
    )
    (net (code "61") (name "unconnected-(S2-NO_2-Pad4)") (class "Default")
      (node (ref "S2") (pin "4") (pinfunction "NO_2_4") (pintype "bidirectional+no_connect"))
    )
    (net (code "62") (name "unconnected-(S4-COM_1-Pad2)") (class "Default")
      (node (ref "S4") (pin "2") (pinfunction "COM_1_2") (pintype "bidirectional+no_connect"))
    )
    (net (code "63") (name "unconnected-(S4-NO_2-Pad4)") (class "Default")
      (node (ref "S4") (pin "4") (pinfunction "NO_2_4") (pintype "bidirectional+no_connect"))
    )
    (net (code "64") (name "unconnected-(S5-COM_1-Pad2)") (class "Default")
      (node (ref "S5") (pin "2") (pinfunction "COM_1_2") (pintype "bidirectional+no_connect"))
    )
    (net (code "65") (name "unconnected-(S5-NO_2-Pad4)") (class "Default")
      (node (ref "S5") (pin "4") (pinfunction "NO_2_4") (pintype "bidirectional+no_connect"))
    )
    (net (code "66") (name "unconnected-(S6-COM_1-Pad2)") (class "Default")
      (node (ref "S6") (pin "2") (pinfunction "COM_1_2") (pintype "bidirectional+no_connect"))
    )
    (net (code "67") (name "unconnected-(S6-NO_2-Pad4)") (class "Default")
      (node (ref "S6") (pin "4") (pinfunction "NO_2_4") (pintype "bidirectional+no_connect"))
    )
    (net (code "68") (name "unconnected-(U1-Pad3)") (class "Default")
      (node (ref "U1") (pin "3") (pinfunction "3_3") (pintype "unspecified"))
    )
    (net (code "69") (name "unconnected-(U1-Pad4)") (class "Default")
      (node (ref "U1") (pin "4") (pinfunction "4_4") (pintype "unspecified"))
    )
    (net (code "70") (name "unconnected-(U1-Pad5)") (class "Default")
      (node (ref "U1") (pin "5") (pinfunction "5_5") (pintype "unspecified"))
    )
    (net (code "71") (name "unconnected-(U1-Pad6)") (class "Default")
      (node (ref "U1") (pin "6") (pinfunction "6_6") (pintype "unspecified"))
    )
    (net (code "72") (name "unconnected-(U1-Pad7)") (class "Default")
      (node (ref "U1") (pin "7") (pinfunction "7_7") (pintype "unspecified"))
    )
    (net (code "73") (name "unconnected-(U1-Pad8)") (class "Default")
      (node (ref "U1") (pin "8") (pinfunction "8_8") (pintype "unspecified"))
    )
    (net (code "74") (name "unconnected-(U1-Pad9)") (class "Default")
      (node (ref "U1") (pin "9") (pinfunction "9_9") (pintype "unspecified"))
    )
    (net (code "75") (name "unconnected-(U1-Pad10)") (class "Default")
      (node (ref "U1") (pin "10") (pinfunction "10_10") (pintype "unspecified"))
    )
    (net (code "76") (name "unconnected-(U1-Pad11)") (class "Default")
      (node (ref "U1") (pin "11") (pinfunction "11_11") (pintype "unspecified"))
    )
    (net (code "77") (name "unconnected-(U1-Pad12)") (class "Default")
      (node (ref "U1") (pin "12") (pinfunction "12_12") (pintype "unspecified"))
    )
    (net (code "78") (name "unconnected-(U1-Pad13)") (class "Default")
      (node (ref "U1") (pin "13") (pinfunction "13_13") (pintype "unspecified"))
    )
    (net (code "79") (name "unconnected-(U1-Pad14)") (class "Default")
      (node (ref "U1") (pin "14") (pinfunction "14_14") (pintype "unspecified"))
    )
    (net (code "80") (name "unconnected-(U1-Pad15)") (class "Default")
      (node (ref "U1") (pin "15") (pinfunction "15_15") (pintype "unspecified"))
    )
    (net (code "81") (name "unconnected-(U1-Pad16)") (class "Default")
      (node (ref "U1") (pin "16") (pinfunction "16_16") (pintype "unspecified"))
    )
    (net (code "82") (name "unconnected-(U1-Pad17)") (class "Default")
      (node (ref "U1") (pin "17") (pinfunction "17_17") (pintype "unspecified"))
    )
    (net (code "83") (name "unconnected-(U1-Pad18)") (class "Default")
      (node (ref "U1") (pin "18") (pinfunction "18_18") (pintype "unspecified"))
    )
    (net (code "84") (name "unconnected-(U1-Pad19)") (class "Default")
      (node (ref "U1") (pin "19") (pinfunction "19_19") (pintype "unspecified"))
    )
    (net (code "85") (name "unconnected-(U1-Pad20)") (class "Default")
      (node (ref "U1") (pin "20") (pinfunction "20_20") (pintype "unspecified"))
    )
    (net (code "86") (name "unconnected-(U1-Pad21)") (class "Default")
      (node (ref "U1") (pin "21") (pinfunction "21_21") (pintype "unspecified"))
    )
    (net (code "87") (name "unconnected-(U1-Pad22)") (class "Default")
      (node (ref "U1") (pin "22") (pinfunction "22_22") (pintype "unspecified"))
    )
    (net (code "88") (name "unconnected-(U2-CTS#-Pad9)") (class "Default")
      (node (ref "U2") (pin "9") (pinfunction "CTS#_9") (pintype "unspecified"))
    )
    (net (code "89") (name "unconnected-(U2-DCD#-Pad12)") (class "Default")
      (node (ref "U2") (pin "12") (pinfunction "DCD#_12") (pintype "unspecified"))
    )
    (net (code "90") (name "unconnected-(U2-DSR#-Pad10)") (class "Default")
      (node (ref "U2") (pin "10") (pinfunction "DSR#_10") (pintype "unspecified"))
    )
    (net (code "91") (name "unconnected-(U2-NC.-Pad7)") (class "Default")
      (node (ref "U2") (pin "7") (pinfunction "NC._7") (pintype "unspecified"))
    )
    (net (code "92") (name "unconnected-(U2-OUT#-Pad8)") (class "Default")
      (node (ref "U2") (pin "8") (pinfunction "OUT#_8") (pintype "unspecified"))
    )
    (net (code "93") (name "unconnected-(U2-R232-Pad15)") (class "Default")
      (node (ref "U2") (pin "15") (pinfunction "R232_15") (pintype "unspecified"))
    )
    (net (code "94") (name "unconnected-(U2-RI#-Pad11)") (class "Default")
      (node (ref "U2") (pin "11") (pinfunction "RI#_11") (pintype "unspecified"))
    )
    (net (code "95") (name "unconnected-(U7-IO3-Pad15)") (class "Default")
      (node (ref "U7") (pin "15") (pinfunction "IO3_15") (pintype "unspecified"))
    )
    (net (code "96") (name "unconnected-(U7-IO19-Pad13)") (class "Default")
      (node (ref "U7") (pin "13") (pinfunction "IO19_13") (pintype "unspecified"))
    )
    (net (code "97") (name "unconnected-(U7-IO20-Pad14)") (class "Default")
      (node (ref "U7") (pin "14") (pinfunction "IO20_14") (pintype "unspecified"))
    )
    (net (code "98") (name "unconnected-(U7-IO35-Pad28)") (class "Default")
      (node (ref "U7") (pin "28") (pinfunction "IO35_28") (pintype "unspecified"))
    )
    (net (code "99") (name "unconnected-(U7-IO36-Pad29)") (class "Default")
      (node (ref "U7") (pin "29") (pinfunction "IO36_29") (pintype "unspecified"))
    )
    (net (code "100") (name "unconnected-(U7-IO37-Pad30)") (class "Default")
      (node (ref "U7") (pin "30") (pinfunction "IO37_30") (pintype "unspecified"))
    )
    (net (code "101") (name "unconnected-(U7-IO39-Pad32)") (class "Default")
      (node (ref "U7") (pin "32") (pinfunction "IO39_32") (pintype "unspecified"))
    )
    (net (code "102") (name "unconnected-(U7-IO40-Pad33)") (class "Default")
      (node (ref "U7") (pin "33") (pinfunction "IO40_33") (pintype "unspecified"))
    )
    (net (code "103") (name "unconnected-(U7-IO41-Pad34)") (class "Default")
      (node (ref "U7") (pin "34") (pinfunction "IO41_34") (pintype "unspecified"))
    )
    (net (code "104") (name "unconnected-(U7-IO42-Pad35)") (class "Default")
      (node (ref "U7") (pin "35") (pinfunction "IO42_35") (pintype "unspecified"))
    )
    (net (code "105") (name "unconnected-(U7-IO45-Pad26)") (class "Default")
      (node (ref "U7") (pin "26") (pinfunction "IO45_26") (pintype "unspecified"))
    )
    (net (code "106") (name "unconnected-(U7-IO46-Pad16)") (class "Default")
      (node (ref "U7") (pin "16") (pinfunction "IO46_16") (pintype "unspecified"))
    )
    (net (code "107") (name "unconnected-(U8-Pad1)") (class "Default")
      (node (ref "U8") (pin "1") (pinfunction "1_1") (pintype "unspecified"))
    )
    (net (code "108") (name "unconnected-(U8-Pad2)") (class "Default")
      (node (ref "U8") (pin "2") (pinfunction "2_2") (pintype "unspecified"))
    )
    (net (code "109") (name "unconnected-(U8-Pad3)") (class "Default")
      (node (ref "U8") (pin "3") (pinfunction "3_3") (pintype "unspecified"))
    )
    (net (code "110") (name "unconnected-(U8-Pad4)") (class "Default")
      (node (ref "U8") (pin "4") (pinfunction "4_4") (pintype "unspecified"))
    )
    (net (code "111") (name "unconnected-(U8-Pad7)") (class "Default")
      (node (ref "U8") (pin "7") (pinfunction "7_7") (pintype "unspecified"))
    )
    (net (code "112") (name "unconnected-(U8-Pad8)") (class "Default")
      (node (ref "U8") (pin "8") (pinfunction "8_8") (pintype "unspecified"))
    )
    (net (code "113") (name "unconnected-(U8-Pad9)") (class "Default")
      (node (ref "U8") (pin "9") (pinfunction "9_9") (pintype "unspecified"))
    )
    (net (code "114") (name "unconnected-(U8-Pad10)") (class "Default")
      (node (ref "U8") (pin "10") (pinfunction "10_10") (pintype "unspecified"))
    )
    (net (code "115") (name "unconnected-(U8-Pad11)") (class "Default")
      (node (ref "U8") (pin "11") (pinfunction "11_11") (pintype "unspecified"))
    )
    (net (code "116") (name "unconnected-(U8-Pad12)") (class "Default")
      (node (ref "U8") (pin "12") (pinfunction "12_12") (pintype "unspecified"))
    )
    (net (code "117") (name "unconnected-(U8-Pad13)") (class "Default")
      (node (ref "U8") (pin "13") (pinfunction "13_13") (pintype "unspecified"))
    )
    (net (code "118") (name "unconnected-(U8-Pad14)") (class "Default")
      (node (ref "U8") (pin "14") (pinfunction "14_14") (pintype "unspecified"))
    )
    (net (code "119") (name "unconnected-(U8-Pad15)") (class "Default")
      (node (ref "U8") (pin "15") (pinfunction "15_15") (pintype "unspecified"))
    )
    (net (code "120") (name "unconnected-(U8-Pad16)") (class "Default")
      (node (ref "U8") (pin "16") (pinfunction "16_16") (pintype "unspecified"))
    )
    (net (code "121") (name "unconnected-(U8-Pad17)") (class "Default")
      (node (ref "U8") (pin "17") (pinfunction "17_17") (pintype "unspecified"))
    )
    (net (code "122") (name "unconnected-(U8-Pad18)") (class "Default")
      (node (ref "U8") (pin "18") (pinfunction "18_18") (pintype "unspecified"))
    )
    (net (code "123") (name "unconnected-(U8-Pad19)") (class "Default")
      (node (ref "U8") (pin "19") (pinfunction "19_19") (pintype "unspecified"))
    )
    (net (code "124") (name "unconnected-(U8-Pad20)") (class "Default")
      (node (ref "U8") (pin "20") (pinfunction "20_20") (pintype "unspecified"))
    )
    (net (code "125") (name "unconnected-(U8-Pad21)") (class "Default")
      (node (ref "U8") (pin "21") (pinfunction "21_21") (pintype "unspecified"))
    )
    (net (code "126") (name "unconnected-(U8-Pad22)") (class "Default")
      (node (ref "U8") (pin "22") (pinfunction "22_22") (pintype "unspecified"))
    )
    (net (code "127") (name "unconnected-(USB1-SUB1-PadA8)") (class "Default")
      (node (ref "USB1") (pin "A8") (pinfunction "SUB1_A8") (pintype "unspecified"))
    )
    (net (code "128") (name "unconnected-(USB1-SUB2-PadB8)") (class "Default")
      (node (ref "USB1") (pin "B8") (pinfunction "SUB2_B8") (pintype "unspecified"))
    )
  )
)
